# interfacez_r2_1.net
KiCad netlist of a schematic drawn in EAGLE
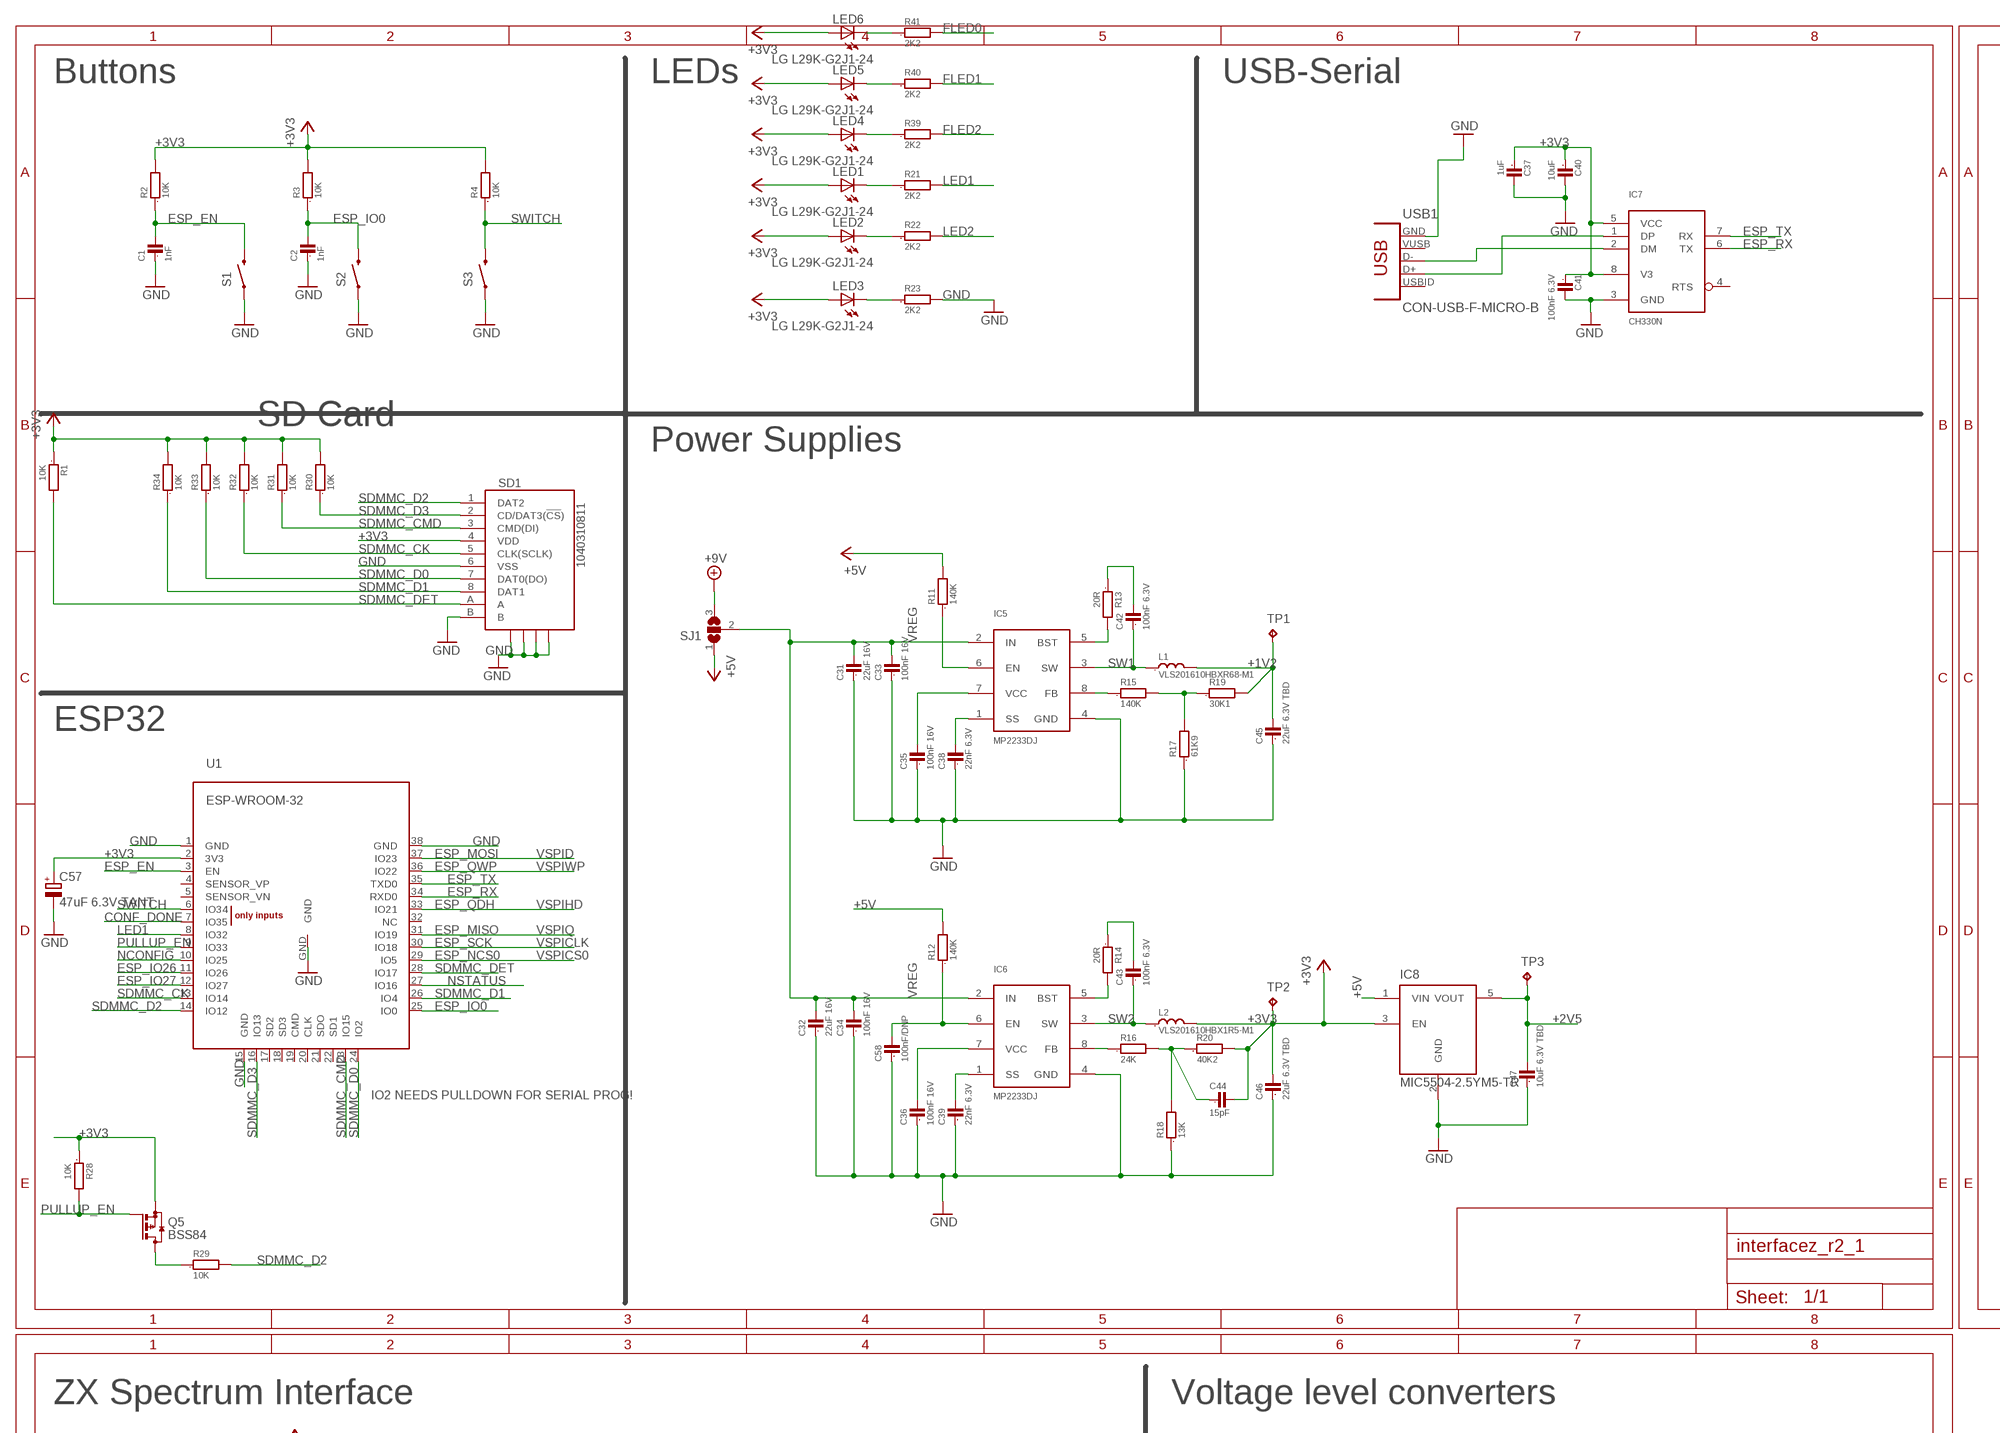
[diagram p0: schematic, sheet 1, part 1 of 3]
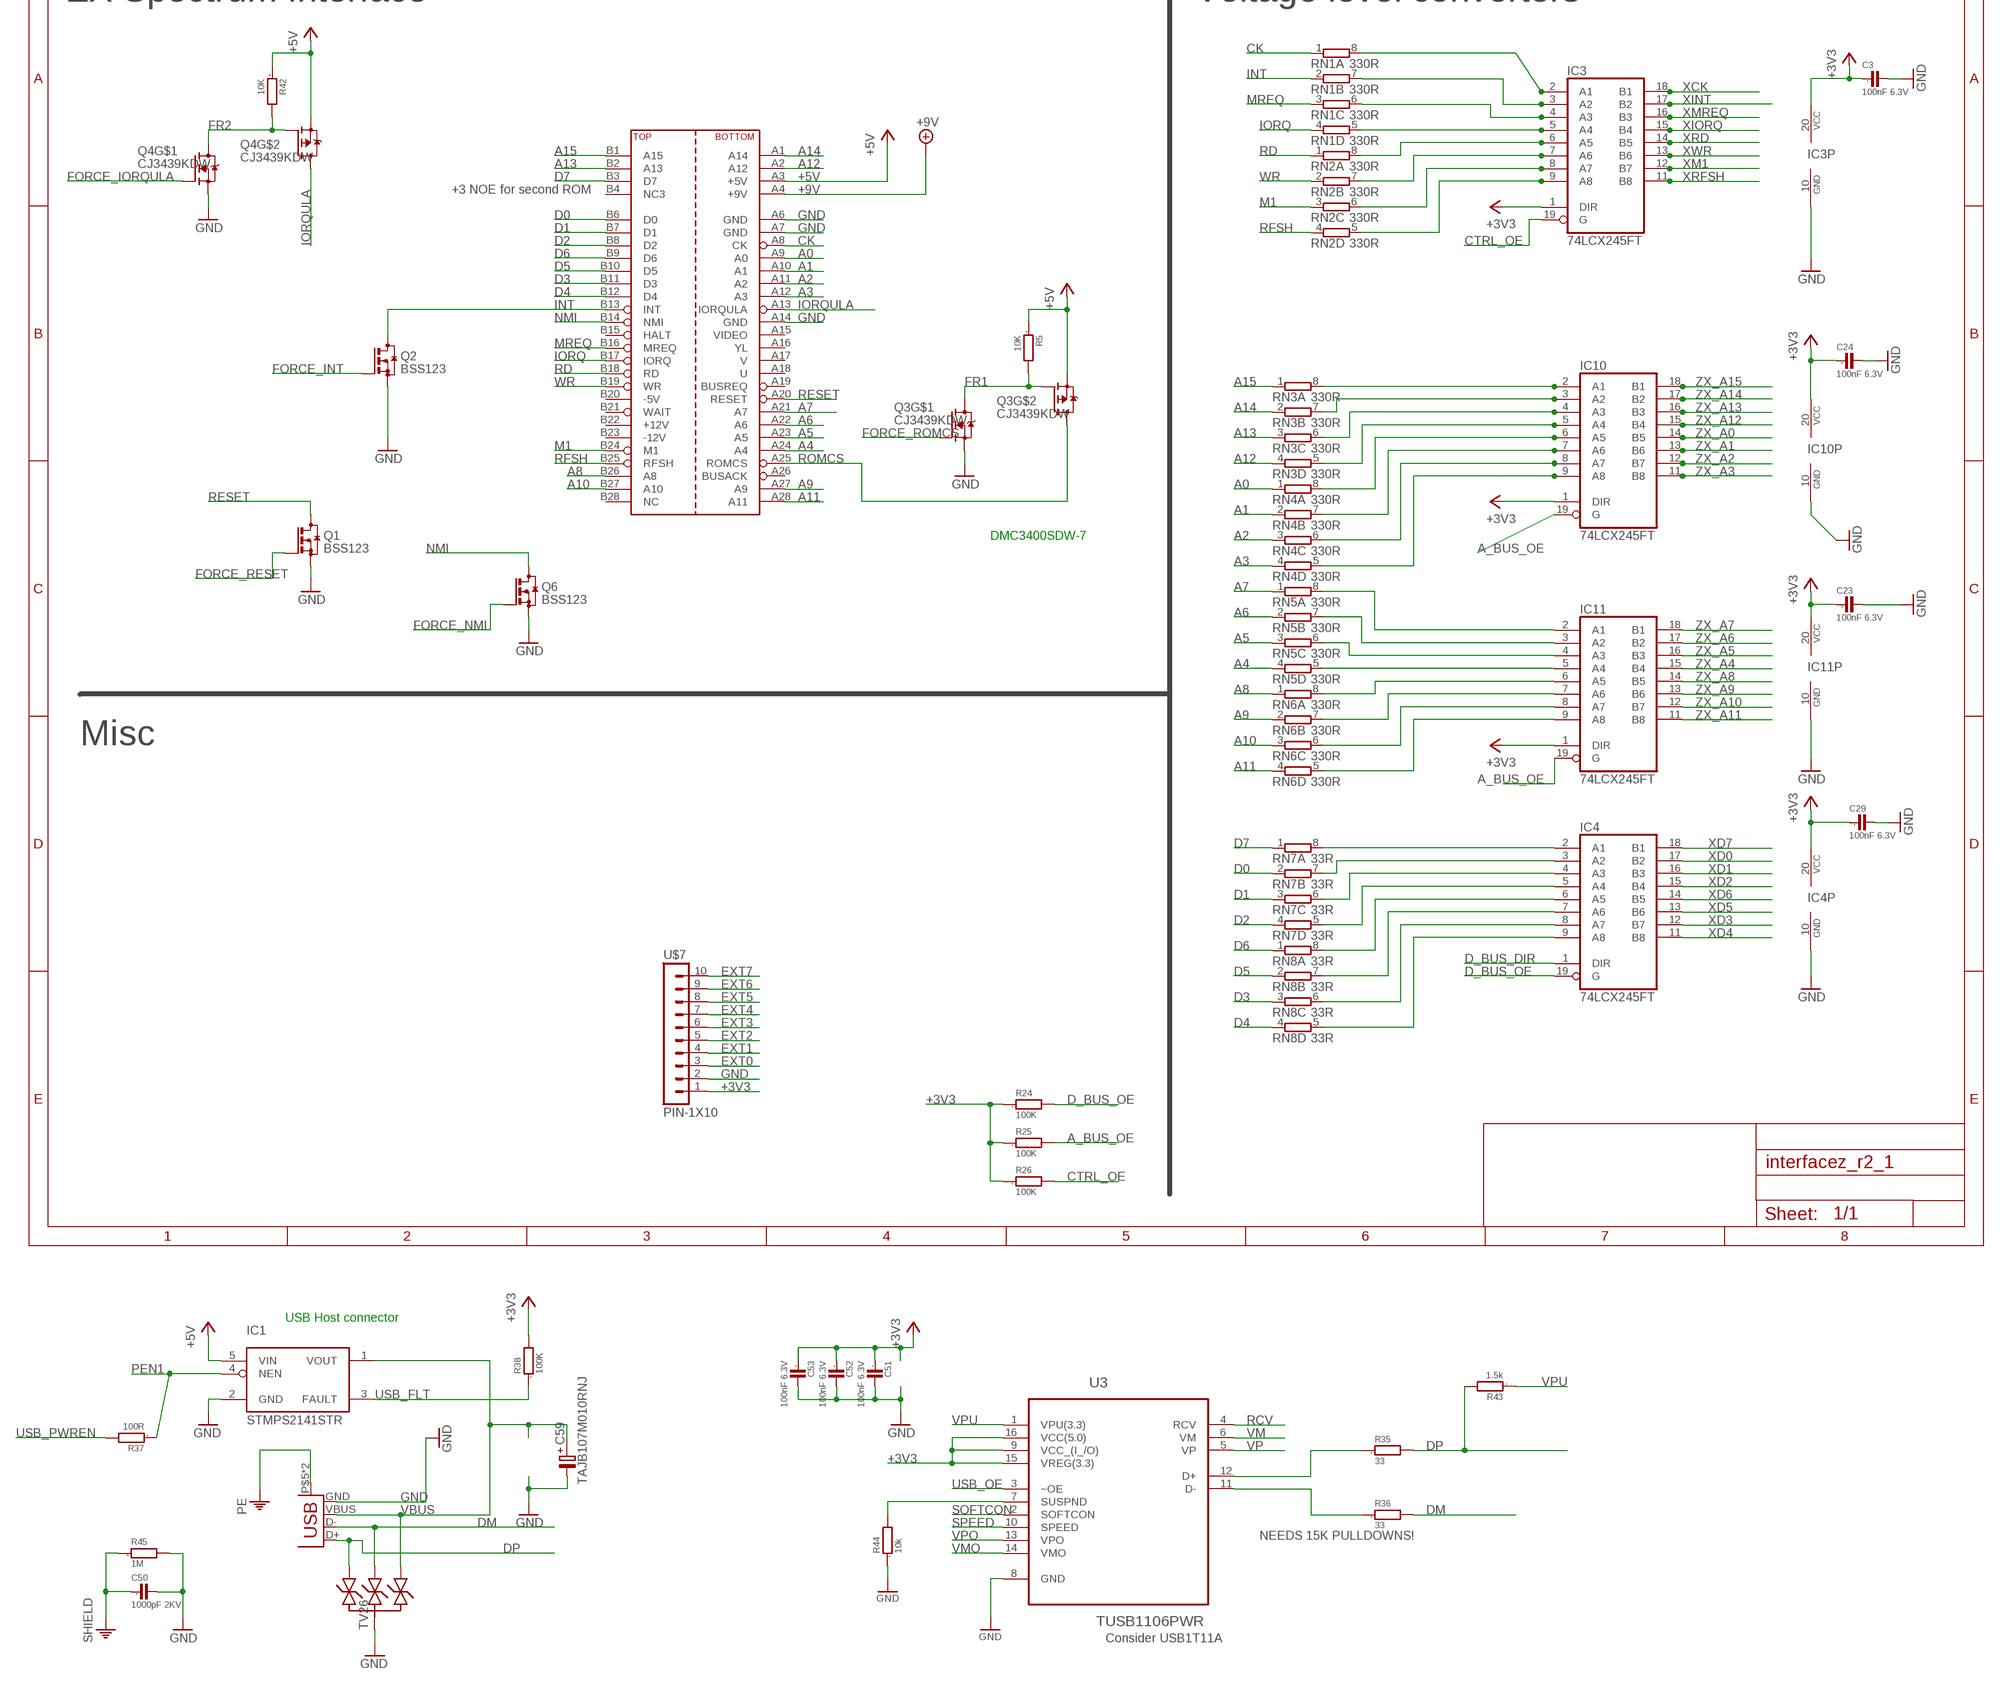
[diagram p1: schematic, sheet 1, part 2 of 3]
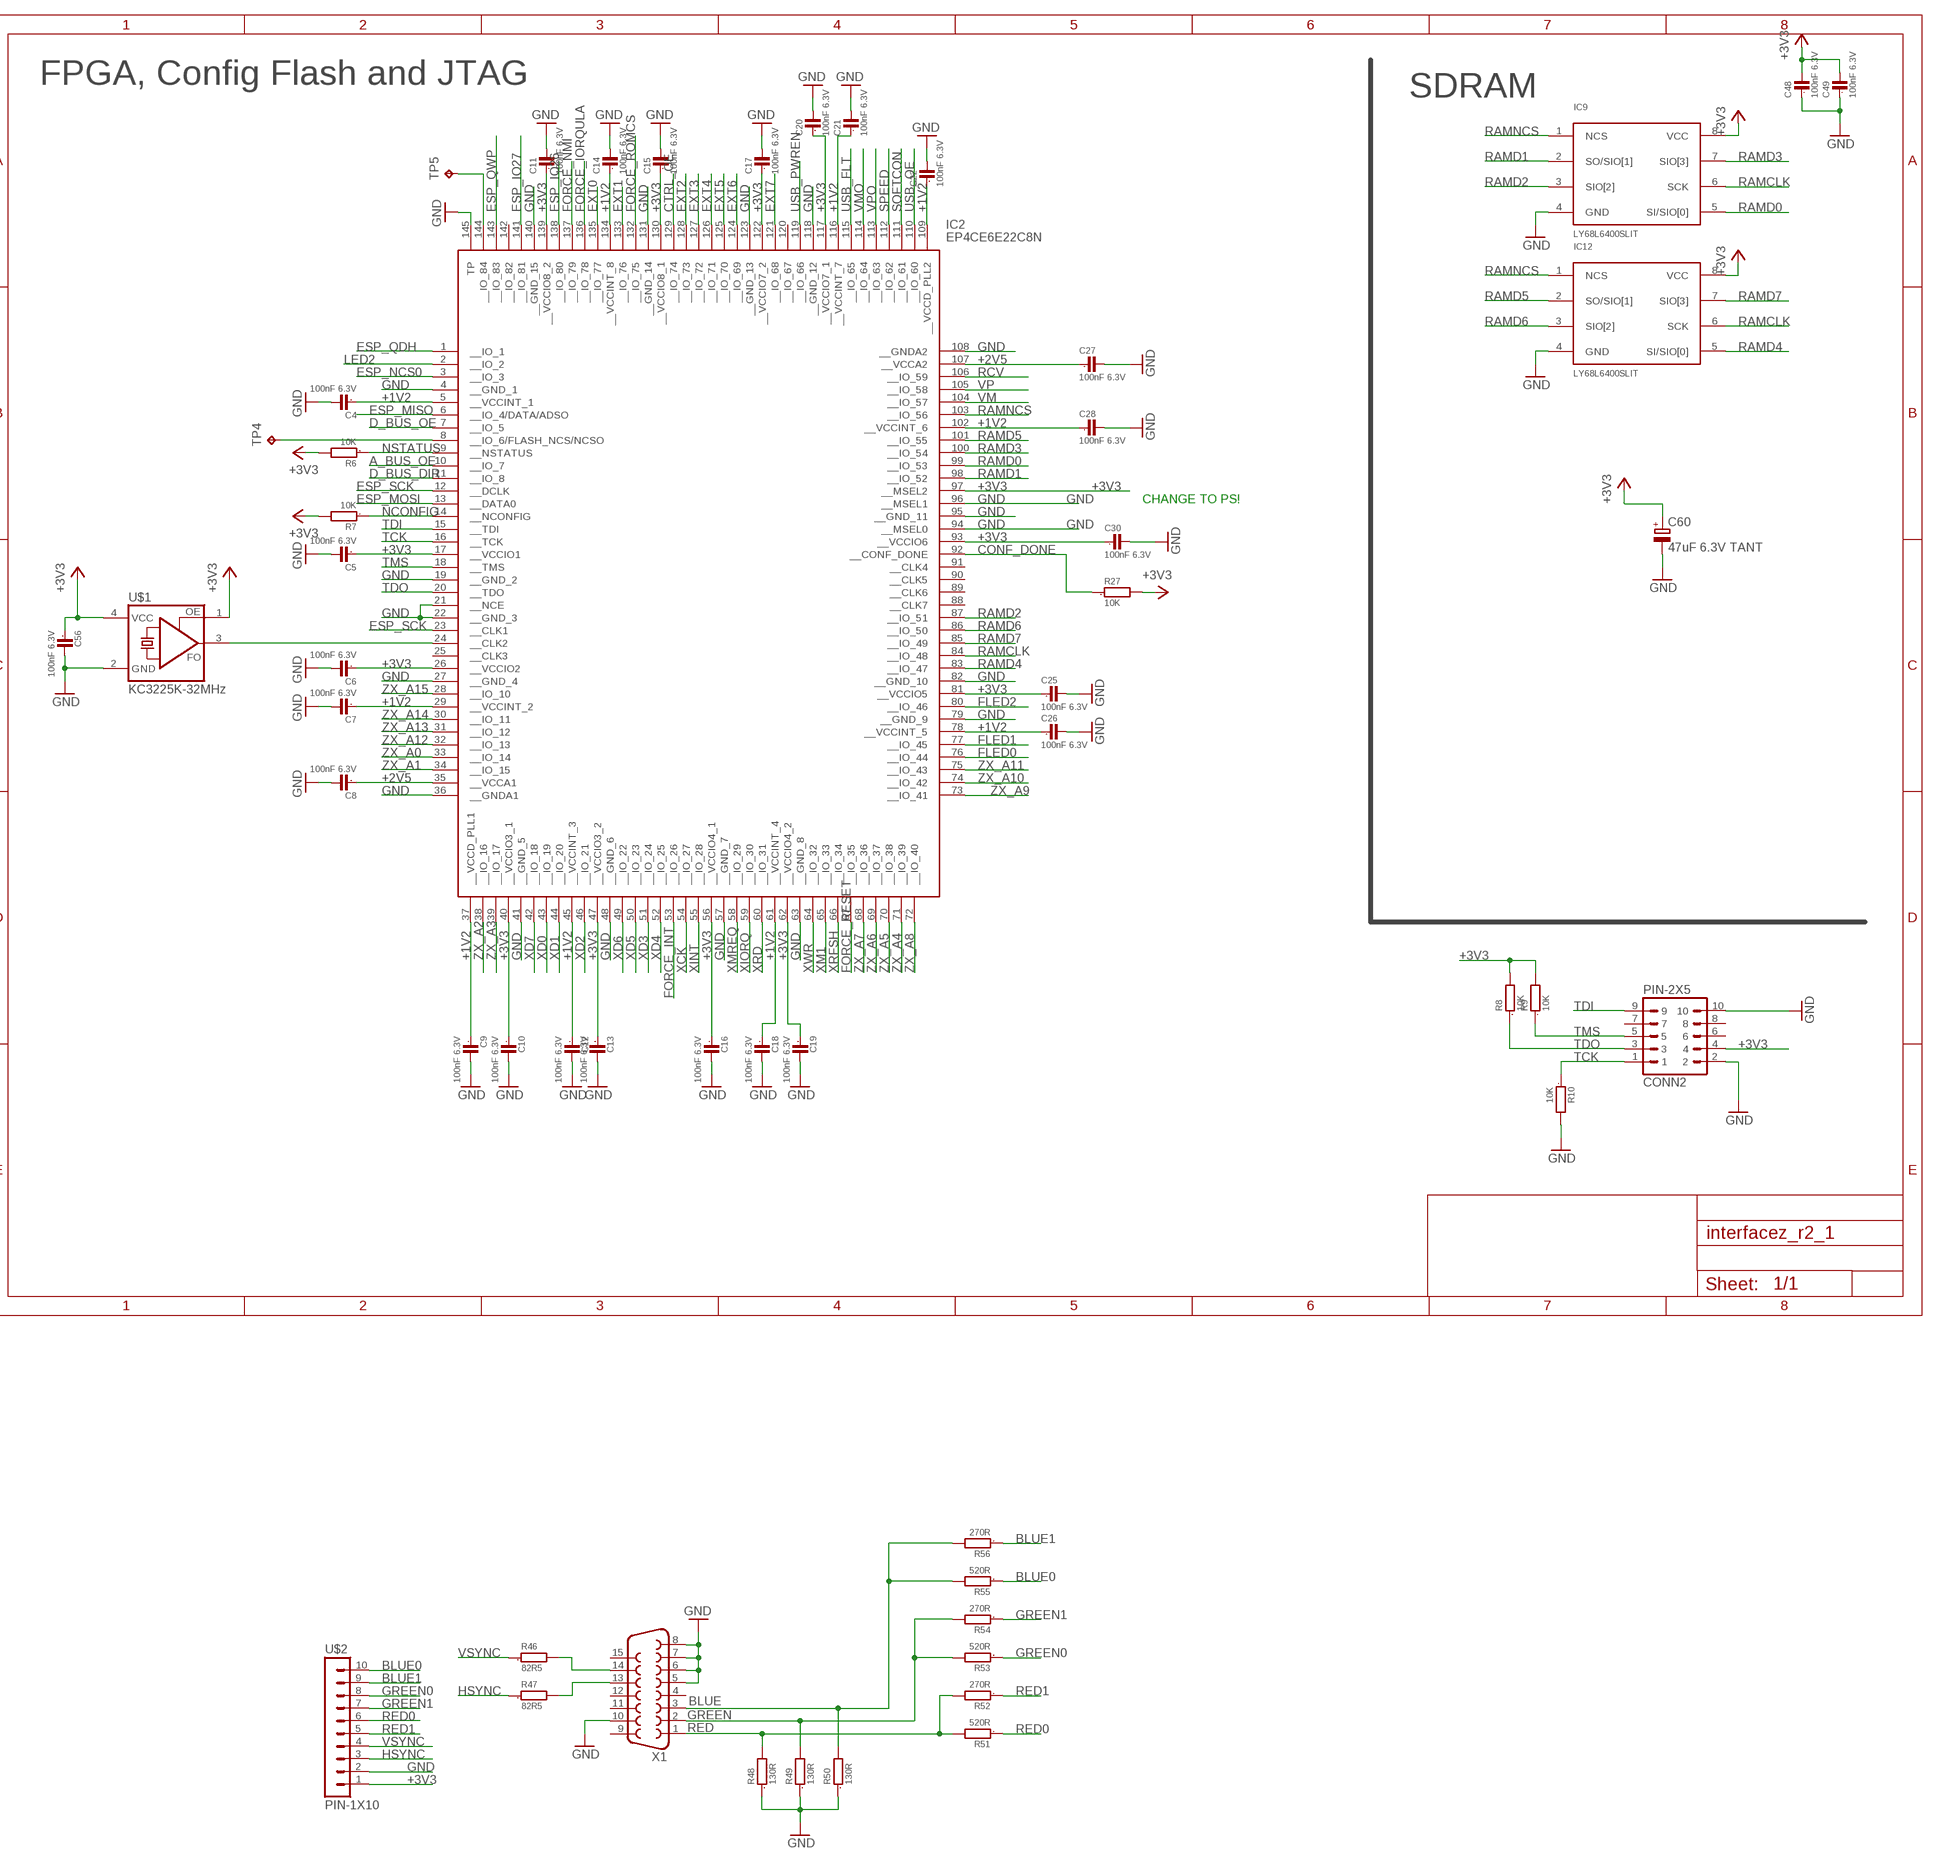
[diagram p2: schematic, sheet 1, part 3 of 3]

(export (version "E")
  (design (tool "Eeschema 10.0.6"))
  (components
    (comp (ref "C1")
      (value "1nF")
      (footprint "eagle-import:0603")
      (libsource (lib "eagle-import") (part "C0603"))
    )
    (comp (ref "C2")
      (value "1nF")
      (footprint "eagle-import:0603")
      (libsource (lib "eagle-import") (part "C0603"))
    )
    (comp (ref "C3")
      (value "100nF 6.3V")
      (footprint "eagle-import:0603")
      (libsource (lib "eagle-import") (part "C0603"))
    )
    (comp (ref "C4")
      (value "100nF 6.3V")
      (footprint "eagle-import:0603")
      (libsource (lib "eagle-import") (part "C0603"))
    )
    (comp (ref "C5")
      (value "100nF 6.3V")
      (footprint "eagle-import:0603")
      (libsource (lib "eagle-import") (part "C0603"))
    )
    (comp (ref "C6")
      (value "100nF 6.3V")
      (footprint "eagle-import:0603")
      (libsource (lib "eagle-import") (part "C0603"))
    )
    (comp (ref "C7")
      (value "100nF 6.3V")
      (footprint "eagle-import:0603")
      (libsource (lib "eagle-import") (part "C0603"))
    )
    (comp (ref "C8")
      (value "100nF 6.3V")
      (footprint "eagle-import:0603")
      (libsource (lib "eagle-import") (part "C0603"))
    )
    (comp (ref "C9")
      (value "100nF 6.3V")
      (footprint "eagle-import:0603")
      (libsource (lib "eagle-import") (part "C0603"))
    )
    (comp (ref "C10")
      (value "100nF 6.3V")
      (footprint "eagle-import:0603")
      (libsource (lib "eagle-import") (part "C0603"))
    )
    (comp (ref "C11")
      (value "100nF 6.3V")
      (footprint "eagle-import:0603")
      (libsource (lib "eagle-import") (part "C0603"))
    )
    (comp (ref "C12")
      (value "100nF 6.3V")
      (footprint "eagle-import:0603")
      (libsource (lib "eagle-import") (part "C0603"))
    )
    (comp (ref "C13")
      (value "100nF 6.3V")
      (footprint "eagle-import:0603")
      (libsource (lib "eagle-import") (part "C0603"))
    )
    (comp (ref "C14")
      (value "100nF 6.3V")
      (footprint "eagle-import:0603")
      (libsource (lib "eagle-import") (part "C0603"))
    )
    (comp (ref "C15")
      (value "100nF 6.3V")
      (footprint "eagle-import:0603")
      (libsource (lib "eagle-import") (part "C0603"))
    )
    (comp (ref "C16")
      (value "100nF 6.3V")
      (footprint "eagle-import:0603")
      (libsource (lib "eagle-import") (part "C0603"))
    )
    (comp (ref "C17")
      (value "100nF 6.3V")
      (footprint "eagle-import:0603")
      (libsource (lib "eagle-import") (part "C0603"))
    )
    (comp (ref "C18")
      (value "100nF 6.3V")
      (footprint "eagle-import:0603")
      (libsource (lib "eagle-import") (part "C0603"))
    )
    (comp (ref "C19")
      (value "100nF 6.3V")
      (footprint "eagle-import:0603")
      (libsource (lib "eagle-import") (part "C0603"))
    )
    (comp (ref "C20")
      (value "100nF 6.3V")
      (footprint "eagle-import:0603")
      (libsource (lib "eagle-import") (part "C0603"))
    )
    (comp (ref "C21")
      (value "100nF 6.3V")
      (footprint "eagle-import:0603")
      (libsource (lib "eagle-import") (part "C0603"))
    )
    (comp (ref "C22")
      (value "100nF 6.3V")
      (footprint "eagle-import:0603")
      (libsource (lib "eagle-import") (part "C0603"))
    )
    (comp (ref "C23")
      (value "100nF 6.3V")
      (footprint "eagle-import:0603")
      (libsource (lib "eagle-import") (part "C0603"))
    )
    (comp (ref "C24")
      (value "100nF 6.3V")
      (footprint "eagle-import:0603")
      (libsource (lib "eagle-import") (part "C0603"))
    )
    (comp (ref "C25")
      (value "100nF 6.3V")
      (footprint "eagle-import:0603")
      (libsource (lib "eagle-import") (part "C0603"))
    )
    (comp (ref "C26")
      (value "100nF 6.3V")
      (footprint "eagle-import:0603")
      (libsource (lib "eagle-import") (part "C0603"))
    )
    (comp (ref "C27")
      (value "100nF 6.3V")
      (footprint "eagle-import:0603")
      (libsource (lib "eagle-import") (part "C0603"))
    )
    (comp (ref "C28")
      (value "100nF 6.3V")
      (footprint "eagle-import:0603")
      (libsource (lib "eagle-import") (part "C0603"))
    )
    (comp (ref "C29")
      (value "100nF 6.3V")
      (footprint "eagle-import:0603")
      (libsource (lib "eagle-import") (part "C0603"))
    )
    (comp (ref "C30")
      (value "100nF 6.3V")
      (footprint "eagle-import:0603")
      (libsource (lib "eagle-import") (part "C0603"))
    )
    (comp (ref "C31")
      (value "22uF 16V")
      (footprint "eagle-import:1210")
      (libsource (lib "eagle-import") (part "C1210"))
    )
    (comp (ref "C32")
      (value "22uF 16V")
      (footprint "eagle-import:1210")
      (libsource (lib "eagle-import") (part "C1210"))
    )
    (comp (ref "C33")
      (value "100nF 16V")
      (footprint "eagle-import:0603")
      (libsource (lib "eagle-import") (part "C0603"))
    )
    (comp (ref "C34")
      (value "100nF 16V")
      (footprint "eagle-import:0603")
      (libsource (lib "eagle-import") (part "C0603"))
    )
    (comp (ref "C35")
      (value "100nF 16V")
      (footprint "eagle-import:0603")
      (libsource (lib "eagle-import") (part "C0603"))
    )
    (comp (ref "C36")
      (value "100nF 16V")
      (footprint "eagle-import:0603")
      (libsource (lib "eagle-import") (part "C0603"))
    )
    (comp (ref "C37")
      (value "1uF")
      (footprint "eagle-import:0603")
      (libsource (lib "eagle-import") (part "C0603"))
    )
    (comp (ref "C38")
      (value "22nF 6.3V")
      (footprint "eagle-import:0603")
      (libsource (lib "eagle-import") (part "C0603"))
    )
    (comp (ref "C39")
      (value "22nF 6.3V")
      (footprint "eagle-import:0603")
      (libsource (lib "eagle-import") (part "C0603"))
    )
    (comp (ref "C40")
      (value "10uF")
      (footprint "eagle-import:0603")
      (libsource (lib "eagle-import") (part "C0603"))
    )
    (comp (ref "C41")
      (value "100nF 6.3V")
      (footprint "eagle-import:0603")
      (libsource (lib "eagle-import") (part "C0603"))
    )
    (comp (ref "C42")
      (value "100nF 6.3V")
      (footprint "eagle-import:0603")
      (libsource (lib "eagle-import") (part "C0603"))
    )
    (comp (ref "C43")
      (value "100nF 6.3V")
      (footprint "eagle-import:0603")
      (libsource (lib "eagle-import") (part "C0603"))
    )
    (comp (ref "C44")
      (value "15pF")
      (footprint "eagle-import:0603")
      (libsource (lib "eagle-import") (part "C0603"))
    )
    (comp (ref "C45")
      (value "22uF 6.3V TBD")
      (footprint "eagle-import:0805")
      (libsource (lib "eagle-import") (part "C0805"))
    )
    (comp (ref "C46")
      (value "22uF 6.3V TBD")
      (footprint "eagle-import:0805")
      (libsource (lib "eagle-import") (part "C0805"))
    )
    (comp (ref "C47")
      (value "10uF 6.3V TBD")
      (footprint "eagle-import:0805")
      (libsource (lib "eagle-import") (part "C0805"))
    )
    (comp (ref "C48")
      (value "100nF 6.3V")
      (footprint "eagle-import:0603")
      (libsource (lib "eagle-import") (part "C0603"))
    )
    (comp (ref "C49")
      (value "100nF 6.3V")
      (footprint "eagle-import:0603")
      (libsource (lib "eagle-import") (part "C0603"))
    )
    (comp (ref "C50")
      (value "1000pF 2KV")
      (footprint "eagle-import:1210")
      (libsource (lib "eagle-import") (part "C1210"))
    )
    (comp (ref "C51")
      (value "100nF 6.3V")
      (footprint "eagle-import:0603")
      (libsource (lib "eagle-import") (part "C0603"))
    )
    (comp (ref "C52")
      (value "100nF 6.3V")
      (footprint "eagle-import:0603")
      (libsource (lib "eagle-import") (part "C0603"))
    )
    (comp (ref "C53")
      (value "100nF 6.3V")
      (footprint "eagle-import:0603")
      (libsource (lib "eagle-import") (part "C0603"))
    )
    (comp (ref "C56")
      (value "100nF 6.3V")
      (footprint "eagle-import:0603")
      (libsource (lib "eagle-import") (part "C0603"))
    )
    (comp (ref "C57")
      (value "47uF 6.3V TANT")
      (footprint "eagle-import:TANT_CASE_A")
      (libsource (lib "eagle-import") (part "TANT_CASE_A"))
    )
    (comp (ref "C58")
      (value "100nF/DNP")
      (footprint "eagle-import:0603")
      (libsource (lib "eagle-import") (part "C0603"))
    )
    (comp (ref "C59")
      (value "TAJB107M010RNJ")
      (footprint "eagle-import:TE-B-3528")
      (libsource (lib "eagle-import") (part "C-PR-SMD-TE-B"))
    )
    (comp (ref "C60")
      (value "47uF 6.3V TANT")
      (footprint "eagle-import:TANT_CASE_A")
      (libsource (lib "eagle-import") (part "TANT_CASE_A"))
    )
    (comp (ref "CONN1")
      (value "ZX_EDGE_DAUGHTERBOARD")
      (footprint "eagle-import:ZX-EDGE-DAUGHTERBOARD")
      (libsource (lib "eagle-import") (part "ZX_EDGE_DAUGHTERBOARD"))
    )
    (comp (ref "CONN2")
      (value "PIN-2X5")
      (footprint "eagle-import:PIN-2X5")
      (libsource (lib "eagle-import") (part "PIN-2X5"))
    )
    (comp (ref "IC1")
      (value "STMPS2141STR")
      (footprint "eagle-import:SOT23-5L")
      (libsource (lib "eagle-import") (part "STMPS2141STR"))
    )
    (comp (ref "IC2")
      (value "EP4CE6E22C8N")
      (footprint "eagle-import:QFP50P2200X2200X165-145N")
      (fields (field (name "MOUSER_PART_NUMBER") "989-EP4CE6E22C8N"))
      (libsource (lib "eagle-import") (part "EP4CE6E22C8N"))
    )
    (comp (ref "IC3")
      (value "74LCX245FT")
      (footprint "eagle-import:TSSOP20")
      (libsource (lib "eagle-import") (part "74245"))
    )
    (comp (ref "IC4")
      (value "74LCX245FT")
      (footprint "eagle-import:TSSOP20")
      (libsource (lib "eagle-import") (part "74245"))
    )
    (comp (ref "IC5")
      (value "MP2233DJ")
      (footprint "eagle-import:SOT23-8L")
      (libsource (lib "eagle-import") (part "MP2233DJ"))
    )
    (comp (ref "IC6")
      (value "MP2233DJ")
      (footprint "eagle-import:SOT23-8L")
      (libsource (lib "eagle-import") (part "MP2233DJ"))
    )
    (comp (ref "IC7")
      (value "CH330N")
      (footprint "eagle-import:SOIC8")
      (libsource (lib "eagle-import") (part "CH330N"))
    )
    (comp (ref "IC8")
      (value "MIC5504-2.5YM5-TR")
      (footprint "eagle-import:SOT23-5L")
      (libsource (lib "eagle-import") (part "MIC550X"))
    )
    (comp (ref "IC9")
      (value "LY68L6400SLIT")
      (footprint "eagle-import:SOIC8")
      (libsource (lib "eagle-import") (part "LY68L6400SLIT"))
    )
    (comp (ref "IC10")
      (value "74LCX245FT")
      (footprint "eagle-import:TSSOP20")
      (libsource (lib "eagle-import") (part "74245"))
    )
    (comp (ref "IC11")
      (value "74LCX245FT")
      (footprint "eagle-import:TSSOP20")
      (libsource (lib "eagle-import") (part "74245"))
    )
    (comp (ref "IC12")
      (value "LY68L6400SLIT")
      (footprint "eagle-import:SOIC8")
      (libsource (lib "eagle-import") (part "LY68L6400SLIT"))
    )
    (comp (ref "L1")
      (value "VLS201610HBXR68-M1")
      (footprint "eagle-import:IND_0806")
      (libsource (lib "eagle-import") (part "VLS201610HBXR68-M1"))
    )
    (comp (ref "L2")
      (value "VLS201610HBX1R5-M1")
      (footprint "eagle-import:IND_0806")
      (libsource (lib "eagle-import") (part "VLS201610HBX1R5-M1"))
    )
    (comp (ref "LED1")
      (value "LG L29K-G2J1-24")
      (footprint "eagle-import:LED-603")
      (libsource (lib "eagle-import") (part "LED-0603"))
    )
    (comp (ref "LED2")
      (value "LG L29K-G2J1-24")
      (footprint "eagle-import:LED-603")
      (libsource (lib "eagle-import") (part "LED-0603"))
    )
    (comp (ref "LED3")
      (value "LG L29K-G2J1-24")
      (footprint "eagle-import:LED-603")
      (libsource (lib "eagle-import") (part "LED-0603"))
    )
    (comp (ref "LED4")
      (value "LG L29K-G2J1-24")
      (footprint "eagle-import:LED-603")
      (libsource (lib "eagle-import") (part "LED-0603"))
    )
    (comp (ref "LED5")
      (value "LG L29K-G2J1-24")
      (footprint "eagle-import:LED-603")
      (libsource (lib "eagle-import") (part "LED-0603"))
    )
    (comp (ref "LED6")
      (value "LG L29K-G2J1-24")
      (footprint "eagle-import:LED-603")
      (libsource (lib "eagle-import") (part "LED-0603"))
    )
    (comp (ref "Q1")
      (value "BSS123")
      (footprint "eagle-import:SOT23")
      (libsource (lib "eagle-import") (part "BSS123"))
    )
    (comp (ref "Q2")
      (value "BSS123")
      (footprint "eagle-import:SOT23")
      (libsource (lib "eagle-import") (part "BSS123"))
    )
    (comp (ref "Q3")
      (value "CJ3439KDW")
      (footprint "eagle-import:SC70-6")
      (libsource (lib "eagle-import") (part "CJ3439KDW"))
    )
    (comp (ref "Q4")
      (value "CJ3439KDW")
      (footprint "eagle-import:SC70-6")
      (libsource (lib "eagle-import") (part "CJ3439KDW"))
    )
    (comp (ref "Q5")
      (value "BSS84")
      (footprint "eagle-import:SOT23")
      (libsource (lib "eagle-import") (part "BSS84"))
    )
    (comp (ref "Q6")
      (value "BSS123")
      (footprint "eagle-import:SOT23")
      (libsource (lib "eagle-import") (part "BSS123"))
    )
    (comp (ref "R1")
      (value "10K")
      (footprint "eagle-import:0603")
      (libsource (lib "eagle-import") (part "R0603"))
    )
    (comp (ref "R2")
      (value "10K")
      (footprint "eagle-import:0603")
      (libsource (lib "eagle-import") (part "R0603"))
    )
    (comp (ref "R3")
      (value "10K")
      (footprint "eagle-import:0603")
      (libsource (lib "eagle-import") (part "R0603"))
    )
    (comp (ref "R4")
      (value "10K")
      (footprint "eagle-import:0603")
      (libsource (lib "eagle-import") (part "R0603"))
    )
    (comp (ref "R5")
      (value "10K")
      (footprint "eagle-import:0603")
      (libsource (lib "eagle-import") (part "R0603"))
    )
    (comp (ref "R6")
      (value "10K")
      (footprint "eagle-import:0603")
      (libsource (lib "eagle-import") (part "R0603"))
    )
    (comp (ref "R7")
      (value "10K")
      (footprint "eagle-import:0603")
      (libsource (lib "eagle-import") (part "R0603"))
    )
    (comp (ref "R8")
      (value "10K")
      (footprint "eagle-import:0603")
      (libsource (lib "eagle-import") (part "R0603"))
    )
    (comp (ref "R9")
      (value "10K")
      (footprint "eagle-import:0603")
      (libsource (lib "eagle-import") (part "R0603"))
    )
    (comp (ref "R10")
      (value "10K")
      (footprint "eagle-import:0603")
      (libsource (lib "eagle-import") (part "R0603"))
    )
    (comp (ref "R11")
      (value "140K")
      (footprint "eagle-import:0603")
      (libsource (lib "eagle-import") (part "R0603"))
    )
    (comp (ref "R12")
      (value "140K")
      (footprint "eagle-import:0603")
      (libsource (lib "eagle-import") (part "R0603"))
    )
    (comp (ref "R13")
      (value "20R")
      (footprint "eagle-import:0603")
      (libsource (lib "eagle-import") (part "R0603"))
    )
    (comp (ref "R14")
      (value "20R")
      (footprint "eagle-import:0603")
      (libsource (lib "eagle-import") (part "R0603"))
    )
    (comp (ref "R15")
      (value "140K")
      (footprint "eagle-import:0603")
      (libsource (lib "eagle-import") (part "R0603"))
    )
    (comp (ref "R16")
      (value "24K")
      (footprint "eagle-import:0603")
      (libsource (lib "eagle-import") (part "R0603"))
    )
    (comp (ref "R17")
      (value "61K9")
      (footprint "eagle-import:0603")
      (libsource (lib "eagle-import") (part "R0603"))
    )
    (comp (ref "R18")
      (value "13K")
      (footprint "eagle-import:0603")
      (libsource (lib "eagle-import") (part "R0603"))
    )
    (comp (ref "R19")
      (value "30K1")
      (footprint "eagle-import:0603")
      (libsource (lib "eagle-import") (part "R0603"))
    )
    (comp (ref "R20")
      (value "40K2")
      (footprint "eagle-import:0603")
      (libsource (lib "eagle-import") (part "R0603"))
    )
    (comp (ref "R21")
      (value "2K2")
      (footprint "eagle-import:0603")
      (libsource (lib "eagle-import") (part "R0603"))
    )
    (comp (ref "R22")
      (value "2K2")
      (footprint "eagle-import:0603")
      (libsource (lib "eagle-import") (part "R0603"))
    )
    (comp (ref "R23")
      (value "2K2")
      (footprint "eagle-import:0603")
      (libsource (lib "eagle-import") (part "R0603"))
    )
    (comp (ref "R24")
      (value "100K")
      (footprint "eagle-import:0603")
      (libsource (lib "eagle-import") (part "R0603"))
    )
    (comp (ref "R25")
      (value "100K")
      (footprint "eagle-import:0603")
      (libsource (lib "eagle-import") (part "R0603"))
    )
    (comp (ref "R26")
      (value "100K")
      (footprint "eagle-import:0603")
      (libsource (lib "eagle-import") (part "R0603"))
    )
    (comp (ref "R27")
      (value "10K")
      (footprint "eagle-import:0603")
      (libsource (lib "eagle-import") (part "R0603"))
    )
    (comp (ref "R28")
      (value "10K")
      (footprint "eagle-import:0603")
      (libsource (lib "eagle-import") (part "R0603"))
    )
    (comp (ref "R29")
      (value "10K")
      (footprint "eagle-import:0603")
      (libsource (lib "eagle-import") (part "R0603"))
    )
    (comp (ref "R30")
      (value "10K")
      (footprint "eagle-import:0603")
      (libsource (lib "eagle-import") (part "R0603"))
    )
    (comp (ref "R31")
      (value "10K")
      (footprint "eagle-import:0603")
      (libsource (lib "eagle-import") (part "R0603"))
    )
    (comp (ref "R32")
      (value "10K")
      (footprint "eagle-import:0603")
      (libsource (lib "eagle-import") (part "R0603"))
    )
    (comp (ref "R33")
      (value "10K")
      (footprint "eagle-import:0603")
      (libsource (lib "eagle-import") (part "R0603"))
    )
    (comp (ref "R34")
      (value "10K")
      (footprint "eagle-import:0603")
      (libsource (lib "eagle-import") (part "R0603"))
    )
    (comp (ref "R35")
      (value "33")
      (footprint "eagle-import:0603")
      (libsource (lib "eagle-import") (part "R0603"))
    )
    (comp (ref "R36")
      (value "33")
      (footprint "eagle-import:0603")
      (libsource (lib "eagle-import") (part "R0603"))
    )
    (comp (ref "R37")
      (value "100R")
      (footprint "eagle-import:0603")
      (libsource (lib "eagle-import") (part "R0603"))
    )
    (comp (ref "R38")
      (value "100K")
      (footprint "eagle-import:0603")
      (libsource (lib "eagle-import") (part "R0603"))
    )
    (comp (ref "R39")
      (value "2K2")
      (footprint "eagle-import:0603")
      (libsource (lib "eagle-import") (part "R0603"))
    )
    (comp (ref "R40")
      (value "2K2")
      (footprint "eagle-import:0603")
      (libsource (lib "eagle-import") (part "R0603"))
    )
    (comp (ref "R41")
      (value "2K2")
      (footprint "eagle-import:0603")
      (libsource (lib "eagle-import") (part "R0603"))
    )
    (comp (ref "R42")
      (value "10K")
      (footprint "eagle-import:0603")
      (libsource (lib "eagle-import") (part "R0603"))
    )
    (comp (ref "R43")
      (value "1.5k")
      (footprint "eagle-import:0603")
      (libsource (lib "eagle-import") (part "R0603"))
    )
    (comp (ref "R44")
      (value "10k")
      (footprint "eagle-import:0603")
      (libsource (lib "eagle-import") (part "R0603"))
    )
    (comp (ref "R45")
      (value "1M")
      (footprint "eagle-import:0805")
      (libsource (lib "eagle-import") (part "R0805"))
    )
    (comp (ref "R46")
      (value "82R5")
      (footprint "eagle-import:0603")
      (libsource (lib "eagle-import") (part "R0603"))
    )
    (comp (ref "R47")
      (value "82R5")
      (footprint "eagle-import:0603")
      (libsource (lib "eagle-import") (part "R0603"))
    )
    (comp (ref "R48")
      (value "130R")
      (footprint "eagle-import:0603")
      (libsource (lib "eagle-import") (part "R0603"))
    )
    (comp (ref "R49")
      (value "130R")
      (footprint "eagle-import:0603")
      (libsource (lib "eagle-import") (part "R0603"))
    )
    (comp (ref "R50")
      (value "130R")
      (footprint "eagle-import:0603")
      (libsource (lib "eagle-import") (part "R0603"))
    )
    (comp (ref "R51")
      (value "520R")
      (footprint "eagle-import:0603")
      (libsource (lib "eagle-import") (part "R0603"))
    )
    (comp (ref "R52")
      (value "270R")
      (footprint "eagle-import:0603")
      (libsource (lib "eagle-import") (part "R0603"))
    )
    (comp (ref "R53")
      (value "520R")
      (footprint "eagle-import:0603")
      (libsource (lib "eagle-import") (part "R0603"))
    )
    (comp (ref "R54")
      (value "270R")
      (footprint "eagle-import:0603")
      (libsource (lib "eagle-import") (part "R0603"))
    )
    (comp (ref "R55")
      (value "520R")
      (footprint "eagle-import:0603")
      (libsource (lib "eagle-import") (part "R0603"))
    )
    (comp (ref "R56")
      (value "270R")
      (footprint "eagle-import:0603")
      (libsource (lib "eagle-import") (part "R0603"))
    )
    (comp (ref "RN1")
      (value "330R")
      (footprint "eagle-import:EXB28V")
      (libsource (lib "eagle-import") (part "4R-NEXB28V"))
    )
    (comp (ref "RN2")
      (value "330R")
      (footprint "eagle-import:EXB28V")
      (libsource (lib "eagle-import") (part "4R-NEXB28V"))
    )
    (comp (ref "RN3")
      (value "330R")
      (footprint "eagle-import:EXB28V")
      (libsource (lib "eagle-import") (part "4R-NEXB28V"))
    )
    (comp (ref "RN4")
      (value "330R")
      (footprint "eagle-import:EXB28V")
      (libsource (lib "eagle-import") (part "4R-NEXB28V"))
    )
    (comp (ref "RN5")
      (value "330R")
      (footprint "eagle-import:EXB28V")
      (libsource (lib "eagle-import") (part "4R-NEXB28V"))
    )
    (comp (ref "RN6")
      (value "330R")
      (footprint "eagle-import:EXB28V")
      (libsource (lib "eagle-import") (part "4R-NEXB28V"))
    )
    (comp (ref "RN7")
      (value "33R")
      (footprint "eagle-import:EXB28V")
      (libsource (lib "eagle-import") (part "4R-NEXB28V"))
    )
    (comp (ref "RN8")
      (value "33R")
      (footprint "eagle-import:EXB28V")
      (libsource (lib "eagle-import") (part "4R-NEXB28V"))
    )
    (comp (ref "S1")
      (value "SWITCHES_SMD-4")
      (footprint "eagle-import:TACTILE_SWITCH_TALL")
      (libsource (lib "eagle-import") (part "SWITCHES_SMD-4"))
    )
    (comp (ref "S2")
      (value "SWITCHES_SMD-4")
      (footprint "eagle-import:TACTILE_SWITCH_TALL")
      (libsource (lib "eagle-import") (part "SWITCHES_SMD-4"))
    )
    (comp (ref "S3")
      (value "SWITCHES_SMD-4")
      (footprint "eagle-import:TACTILE_SWITCH_TALL")
      (libsource (lib "eagle-import") (part "SWITCHES_SMD-4"))
    )
    (comp (ref "SD1")
      (value "1040310811")
      (footprint "eagle-import:1040310811")
      (libsource (lib "eagle-import") (part "1040310811"))
    )
    (comp (ref "SJ1")
      (value "SJ2W")
      (footprint "eagle-import:SJ_2")
      (libsource (lib "eagle-import") (part "SJ2W"))
    )
    (comp (ref "TP1")
      (value "TPTP12R")
      (footprint "eagle-import:TP12R")
      (libsource (lib "eagle-import") (part "TPTP12R"))
    )
    (comp (ref "TP2")
      (value "TPTP12R")
      (footprint "eagle-import:TP12R")
      (libsource (lib "eagle-import") (part "TPTP12R"))
    )
    (comp (ref "TP3")
      (value "TPTP12R")
      (footprint "eagle-import:TP12R")
      (libsource (lib "eagle-import") (part "TPTP12R"))
    )
    (comp (ref "TP4")
      (value "TPTP08R")
      (footprint "eagle-import:TP08R")
      (libsource (lib "eagle-import") (part "TPTP08R"))
    )
    (comp (ref "TP5")
      (value "TPTP08R")
      (footprint "eagle-import:TP08R")
      (libsource (lib "eagle-import") (part "TPTP08R"))
    )
    (comp (ref "TV26")
      (value "SP0503BAHT")
      (footprint "eagle-import:SP0503")
      (libsource (lib "eagle-import") (part "SP0503BAHT"))
    )
    (comp (ref "U$1")
      (value "KC3225K-32MHz")
      (footprint "eagle-import:KC3225K")
      (libsource (lib "eagle-import") (part "KC3225K"))
    )
    (comp (ref "U$2")
      (value "PIN-1X10")
      (footprint "eagle-import:PIN-1X10")
      (libsource (lib "eagle-import") (part "PIN-1X10"))
    )
    (comp (ref "U$7")
      (value "PIN-1X10")
      (footprint "eagle-import:PIN-1X10")
      (libsource (lib "eagle-import") (part "PIN-1X10"))
    )
    (comp (ref "U1")
      (value "ESP-WROOM-32")
      (footprint "eagle-import:ESP-WROOM-32")
      (libsource (lib "eagle-import") (part "ESP-WROOM-32"))
    )
    (comp (ref "U3")
      (value "TUSB1106PWR")
      (footprint "eagle-import:SOP65P640X120-16N")
      (libsource (lib "eagle-import") (part "TUSB1106PWR"))
    )
    (comp (ref "USB1")
      (value "CON-USB-F-MICRO-B")
      (footprint "eagle-import:CONN_USB_MICRO-B")
      (libsource (lib "eagle-import") (part "CON-USB-F-MICRO-B"))
    )
    (comp (ref "USB2")
      (value "USB-A-H")
      (footprint "eagle-import:USB-A-H")
      (libsource (lib "eagle-import") (part "USB-A-H"))
    )
    (comp (ref "X1")
      (value "F15HDH")
      (footprint "eagle-import:HDF15H")
      (libsource (lib "eagle-import") (part "F15HDH"))
    )
  )
  (nets
    (net (code "1") (name "+3V3") (class "Default")
      (node (ref "C10") (pin "1") (pinfunction "1_1") (pintype "passive"))
      (node (ref "C11") (pin "1") (pinfunction "1_1") (pintype "passive"))
      (node (ref "C13") (pin "1") (pinfunction "1_1") (pintype "passive"))
      (node (ref "C15") (pin "1") (pinfunction "1_1") (pintype "passive"))
      (node (ref "C16") (pin "1") (pinfunction "1_1") (pintype "passive"))
      (node (ref "C17") (pin "1") (pinfunction "1_1") (pintype "passive"))
      (node (ref "C19") (pin "1") (pinfunction "1_1") (pintype "passive"))
      (node (ref "C20") (pin "1") (pinfunction "1_1") (pintype "passive"))
      (node (ref "C23") (pin "1") (pinfunction "1_1") (pintype "passive"))
      (node (ref "C24") (pin "1") (pinfunction "1_1") (pintype "passive"))
      (node (ref "C25") (pin "1") (pinfunction "1_1") (pintype "passive"))
      (node (ref "C29") (pin "1") (pinfunction "1_1") (pintype "passive"))
      (node (ref "C3") (pin "1") (pinfunction "1_1") (pintype "passive"))
      (node (ref "C30") (pin "1") (pinfunction "1_1") (pintype "passive"))
      (node (ref "C37") (pin "1") (pinfunction "1_1") (pintype "passive"))
      (node (ref "C40") (pin "1") (pinfunction "1_1") (pintype "passive"))
      (node (ref "C41") (pin "1") (pinfunction "1_1") (pintype "passive"))
      (node (ref "C44") (pin "2") (pinfunction "2_2") (pintype "passive"))
      (node (ref "C46") (pin "2") (pinfunction "2_2") (pintype "passive"))
      (node (ref "C48") (pin "2") (pinfunction "2_2") (pintype "passive"))
      (node (ref "C49") (pin "2") (pinfunction "2_2") (pintype "passive"))
      (node (ref "C5") (pin "1") (pinfunction "1_1") (pintype "passive"))
      (node (ref "C51") (pin "1") (pinfunction "1_1") (pintype "passive"))
      (node (ref "C52") (pin "1") (pinfunction "1_1") (pintype "passive"))
      (node (ref "C53") (pin "1") (pinfunction "1_1") (pintype "passive"))
      (node (ref "C56") (pin "1") (pinfunction "1_1") (pintype "passive"))
      (node (ref "C57") (pin "PLUS") (pinfunction "+_PLUS") (pintype "passive"))
      (node (ref "C6") (pin "1") (pinfunction "1_1") (pintype "passive"))
      (node (ref "C60") (pin "PLUS") (pinfunction "+_PLUS") (pintype "passive"))
      (node (ref "CONN2") (pin "4") (pinfunction "4_4") (pintype "passive"))
      (node (ref "IC10") (pin "1") (pinfunction "DIR_1") (pintype "input"))
      (node (ref "IC10") (pin "20") (pinfunction "VCC_20") (pintype "power_in"))
      (node (ref "IC11") (pin "1") (pinfunction "DIR_1") (pintype "input"))
      (node (ref "IC11") (pin "20") (pinfunction "VCC_20") (pintype "power_in"))
      (node (ref "IC12") (pin "8") (pinfunction "VCC_8") (pintype "power_in"))
      (node (ref "IC2") (pin "117") (pinfunction "__VCCIO7_1_117") (pintype "power_in"))
      (node (ref "IC2") (pin "122") (pinfunction "__VCCIO7_2_122") (pintype "power_in"))
      (node (ref "IC2") (pin "130") (pinfunction "__VCCIO8_1_130") (pintype "power_in"))
      (node (ref "IC2") (pin "139") (pinfunction "__VCCIO8_2_139") (pintype "power_in"))
      (node (ref "IC2") (pin "17") (pinfunction "__VCCIO1_17") (pintype "power_in"))
      (node (ref "IC2") (pin "26") (pinfunction "__VCCIO2_26") (pintype "power_in"))
      (node (ref "IC2") (pin "40") (pinfunction "__VCCIO3_1_40") (pintype "power_in"))
      (node (ref "IC2") (pin "47") (pinfunction "__VCCIO3_2_47") (pintype "power_in"))
      (node (ref "IC2") (pin "56") (pinfunction "__VCCIO4_1_56") (pintype "power_in"))
      (node (ref "IC2") (pin "62") (pinfunction "__VCCIO4_2_62") (pintype "power_in"))
      (node (ref "IC2") (pin "81") (pinfunction "__VCCIO5_81") (pintype "power_in"))
      (node (ref "IC2") (pin "93") (pinfunction "__VCCIO6_93") (pintype "power_in"))
      (node (ref "IC2") (pin "97") (pinfunction "__MSEL2_97") (pintype "bidirectional"))
      (node (ref "IC3") (pin "1") (pinfunction "DIR_1") (pintype "input"))
      (node (ref "IC3") (pin "20") (pinfunction "VCC_20") (pintype "power_in"))
      (node (ref "IC4") (pin "20") (pinfunction "VCC_20") (pintype "power_in"))
      (node (ref "IC7") (pin "5") (pinfunction "VCC_5") (pintype "power_in"))
      (node (ref "IC7") (pin "8") (pinfunction "V3_8") (pintype "passive"))
      (node (ref "IC8") (pin "3") (pinfunction "EN_3") (pintype "input"))
      (node (ref "IC9") (pin "8") (pinfunction "VCC_8") (pintype "power_in"))
      (node (ref "L2") (pin "P$2") (pinfunction "2_P$2") (pintype "passive"))
      (node (ref "LED1") (pin "A") (pinfunction "A_A") (pintype "passive"))
      (node (ref "LED2") (pin "A") (pinfunction "A_A") (pintype "passive"))
      (node (ref "LED3") (pin "A") (pinfunction "A_A") (pintype "passive"))
      (node (ref "LED4") (pin "A") (pinfunction "A_A") (pintype "passive"))
      (node (ref "LED5") (pin "A") (pinfunction "A_A") (pintype "passive"))
      (node (ref "LED6") (pin "A") (pinfunction "A_A") (pintype "passive"))
      (node (ref "Q5") (pin "2") (pinfunction "S_2") (pintype "passive"))
      (node (ref "R1") (pin "1") (pinfunction "1_1") (pintype "passive"))
      (node (ref "R2") (pin "2") (pinfunction "2_2") (pintype "passive"))
      (node (ref "R20") (pin "2") (pinfunction "2_2") (pintype "passive"))
      (node (ref "R24") (pin "1") (pinfunction "1_1") (pintype "passive"))
      (node (ref "R25") (pin "1") (pinfunction "1_1") (pintype "passive"))
      (node (ref "R26") (pin "1") (pinfunction "1_1") (pintype "passive"))
      (node (ref "R27") (pin "2") (pinfunction "2_2") (pintype "passive"))
      (node (ref "R28") (pin "1") (pinfunction "1_1") (pintype "passive"))
      (node (ref "R3") (pin "2") (pinfunction "2_2") (pintype "passive"))
      (node (ref "R30") (pin "2") (pinfunction "2_2") (pintype "passive"))
      (node (ref "R31") (pin "2") (pinfunction "2_2") (pintype "passive"))
      (node (ref "R32") (pin "2") (pinfunction "2_2") (pintype "passive"))
      (node (ref "R33") (pin "2") (pinfunction "2_2") (pintype "passive"))
      (node (ref "R34") (pin "2") (pinfunction "2_2") (pintype "passive"))
      (node (ref "R38") (pin "2") (pinfunction "2_2") (pintype "passive"))
      (node (ref "R4") (pin "2") (pinfunction "2_2") (pintype "passive"))
      (node (ref "R6") (pin "2") (pinfunction "2_2") (pintype "passive"))
      (node (ref "R7") (pin "2") (pinfunction "2_2") (pintype "passive"))
      (node (ref "R8") (pin "2") (pinfunction "2_2") (pintype "passive"))
      (node (ref "R9") (pin "2") (pinfunction "2_2") (pintype "passive"))
      (node (ref "SD1") (pin "4") (pinfunction "VDD_4") (pintype "power_in"))
      (node (ref "TP2") (pin "TP") (pinfunction "TP_TP") (pintype "input"))
      (node (ref "U$1") (pin "1") (pinfunction "OE_1") (pintype "input"))
      (node (ref "U$1") (pin "4") (pinfunction "VCC_4") (pintype "power_in"))
      (node (ref "U$2") (pin "1") (pinfunction "1_1") (pintype "passive"))
      (node (ref "U$7") (pin "1") (pinfunction "1_1") (pintype "passive"))
      (node (ref "U1") (pin "2") (pinfunction "3V3_2") (pintype "bidirectional"))
      (node (ref "U3") (pin "15") (pinfunction "VREG(3.3)_15") (pintype "power_in"))
      (node (ref "U3") (pin "16") (pinfunction "VCC(5.0)_16") (pintype "power_in"))
      (node (ref "U3") (pin "9") (pinfunction "VCC_(I_/O)_9") (pintype "power_in"))
    )
    (net (code "2") (name "+5V") (class "Default")
      (node (ref "CONN1") (pin "A3") (pinfunction "+5V_A3") (pintype "power_in"))
      (node (ref "IC1") (pin "5") (pinfunction "VIN_5") (pintype "power_in"))
      (node (ref "IC8") (pin "1") (pinfunction "VIN_1") (pintype "power_in"))
      (node (ref "Q3") (pin "4") (pinfunction "S_4") (pintype "passive"))
      (node (ref "Q4") (pin "4") (pinfunction "S_4") (pintype "passive"))
      (node (ref "R11") (pin "2") (pinfunction "2_2") (pintype "passive"))
      (node (ref "R12") (pin "2") (pinfunction "2_2") (pintype "passive"))
      (node (ref "R42") (pin "1") (pinfunction "1_1") (pintype "passive"))
      (node (ref "R5") (pin "1") (pinfunction "1_1") (pintype "passive"))
      (node (ref "SJ1") (pin "1") (pinfunction "1_1") (pintype "passive"))
    )
    (net (code "3") (name "+9V") (class "Default")
      (node (ref "CONN1") (pin "A4") (pinfunction "+9V_A4") (pintype "power_in"))
      (node (ref "SJ1") (pin "3") (pinfunction "3_3") (pintype "passive"))
    )
    (net (code "4") (name "/+1V2") (class "Default")
      (node (ref "C12") (pin "1") (pinfunction "1_1") (pintype "passive"))
      (node (ref "C14") (pin "1") (pinfunction "1_1") (pintype "passive"))
      (node (ref "C18") (pin "1") (pinfunction "1_1") (pintype "passive"))
      (node (ref "C21") (pin "1") (pinfunction "1_1") (pintype "passive"))
      (node (ref "C22") (pin "1") (pinfunction "1_1") (pintype "passive"))
      (node (ref "C26") (pin "1") (pinfunction "1_1") (pintype "passive"))
      (node (ref "C28") (pin "1") (pinfunction "1_1") (pintype "passive"))
      (node (ref "C4") (pin "1") (pinfunction "1_1") (pintype "passive"))
      (node (ref "C45") (pin "2") (pinfunction "2_2") (pintype "passive"))
      (node (ref "C7") (pin "1") (pinfunction "1_1") (pintype "passive"))
      (node (ref "C9") (pin "1") (pinfunction "1_1") (pintype "passive"))
      (node (ref "IC2") (pin "102") (pinfunction "__VCCINT_6_102") (pintype "power_in"))
      (node (ref "IC2") (pin "109") (pinfunction "__VCCD_PLL2_109") (pintype "power_in"))
      (node (ref "IC2") (pin "116") (pinfunction "__VCCINT_7_116") (pintype "power_in"))
      (node (ref "IC2") (pin "134") (pinfunction "__VCCINT_8_134") (pintype "power_in"))
      (node (ref "IC2") (pin "29") (pinfunction "__VCCINT_2_29") (pintype "power_in"))
      (node (ref "IC2") (pin "37") (pinfunction "__VCCD_PLL1_37") (pintype "power_in"))
      (node (ref "IC2") (pin "45") (pinfunction "__VCCINT_3_45") (pintype "power_in"))
      (node (ref "IC2") (pin "5") (pinfunction "__VCCINT_1_5") (pintype "power_in"))
      (node (ref "IC2") (pin "61") (pinfunction "__VCCINT_4_61") (pintype "power_in"))
      (node (ref "IC2") (pin "78") (pinfunction "__VCCINT_5_78") (pintype "power_in"))
      (node (ref "L1") (pin "P$2") (pinfunction "2_P$2") (pintype "passive"))
      (node (ref "R19") (pin "2") (pinfunction "2_2") (pintype "passive"))
      (node (ref "TP1") (pin "TP") (pinfunction "TP_TP") (pintype "input"))
    )
    (net (code "5") (name "/+2V5") (class "Default")
      (node (ref "C27") (pin "1") (pinfunction "1_1") (pintype "passive"))
      (node (ref "C47") (pin "2") (pinfunction "2_2") (pintype "passive"))
      (node (ref "C8") (pin "1") (pinfunction "1_1") (pintype "passive"))
      (node (ref "IC2") (pin "107") (pinfunction "__VCCA2_107") (pintype "power_in"))
      (node (ref "IC2") (pin "35") (pinfunction "__VCCA1_35") (pintype "power_in"))
      (node (ref "IC8") (pin "5") (pinfunction "VOUT_5") (pintype "power_in"))
      (node (ref "TP3") (pin "TP") (pinfunction "TP_TP") (pintype "input"))
    )
    (net (code "6") (name "/+12V") (class "Default")
      (node (ref "CONN1") (pin "B22") (pinfunction "+12V_B22") (pintype "power_in"))
    )
    (net (code "7") (name "/-5V") (class "Default")
      (node (ref "CONN1") (pin "B20") (pinfunction "-5V_B20") (pintype "power_in"))
    )
    (net (code "8") (name "/-12V") (class "Default")
      (node (ref "CONN1") (pin "B23") (pinfunction "-12V_B23") (pintype "power_in"))
    )
    (net (code "9") (name "/A0") (class "Default")
      (node (ref "CONN1") (pin "A9") (pinfunction "A0_A9") (pintype "bidirectional"))
      (node (ref "RN4") (pin "1") (pinfunction "1_1") (pintype "passive"))
    )
    (net (code "10") (name "/A1") (class "Default")
      (node (ref "CONN1") (pin "A10") (pinfunction "A1_A10") (pintype "bidirectional"))
      (node (ref "RN4") (pin "2") (pinfunction "1_2") (pintype "passive"))
    )
    (net (code "11") (name "/A2") (class "Default")
      (node (ref "CONN1") (pin "A11") (pinfunction "A2_A11") (pintype "bidirectional"))
      (node (ref "RN4") (pin "3") (pinfunction "1_3") (pintype "passive"))
    )
    (net (code "12") (name "/A3") (class "Default")
      (node (ref "CONN1") (pin "A12") (pinfunction "A3_A12") (pintype "bidirectional"))
      (node (ref "RN4") (pin "4") (pinfunction "1_4") (pintype "passive"))
    )
    (net (code "13") (name "/A4") (class "Default")
      (node (ref "CONN1") (pin "A24") (pinfunction "A4_A24") (pintype "bidirectional"))
      (node (ref "RN5") (pin "4") (pinfunction "1_4") (pintype "passive"))
    )
    (net (code "14") (name "/A5") (class "Default")
      (node (ref "CONN1") (pin "A23") (pinfunction "A5_A23") (pintype "bidirectional"))
      (node (ref "RN5") (pin "3") (pinfunction "1_3") (pintype "passive"))
    )
    (net (code "15") (name "/A6") (class "Default")
      (node (ref "CONN1") (pin "A22") (pinfunction "A6_A22") (pintype "bidirectional"))
      (node (ref "RN5") (pin "2") (pinfunction "1_2") (pintype "passive"))
    )
    (net (code "16") (name "/A7") (class "Default")
      (node (ref "CONN1") (pin "A21") (pinfunction "A7_A21") (pintype "bidirectional"))
      (node (ref "RN5") (pin "1") (pinfunction "1_1") (pintype "passive"))
    )
    (net (code "17") (name "/A8") (class "Default")
      (node (ref "CONN1") (pin "B26") (pinfunction "A8_B26") (pintype "bidirectional"))
      (node (ref "RN6") (pin "1") (pinfunction "1_1") (pintype "passive"))
    )
    (net (code "18") (name "/A9") (class "Default")
      (node (ref "CONN1") (pin "A27") (pinfunction "A9_A27") (pintype "bidirectional"))
      (node (ref "RN6") (pin "2") (pinfunction "1_2") (pintype "passive"))
    )
    (net (code "19") (name "/A10") (class "Default")
      (node (ref "CONN1") (pin "B27") (pinfunction "A10_B27") (pintype "bidirectional"))
      (node (ref "RN6") (pin "3") (pinfunction "1_3") (pintype "passive"))
    )
    (net (code "20") (name "/A11") (class "Default")
      (node (ref "CONN1") (pin "A28") (pinfunction "A11_A28") (pintype "bidirectional"))
      (node (ref "RN6") (pin "4") (pinfunction "1_4") (pintype "passive"))
    )
    (net (code "21") (name "/A12") (class "Default")
      (node (ref "CONN1") (pin "A2") (pinfunction "A12_A2") (pintype "bidirectional"))
      (node (ref "RN3") (pin "4") (pinfunction "1_4") (pintype "passive"))
    )
    (net (code "22") (name "/A13") (class "Default")
      (node (ref "CONN1") (pin "B2") (pinfunction "A13_B2") (pintype "bidirectional"))
      (node (ref "RN3") (pin "3") (pinfunction "1_3") (pintype "passive"))
    )
    (net (code "23") (name "/A14") (class "Default")
      (node (ref "CONN1") (pin "A1") (pinfunction "A14_A1") (pintype "bidirectional"))
      (node (ref "RN3") (pin "2") (pinfunction "1_2") (pintype "passive"))
    )
    (net (code "24") (name "/A15") (class "Default")
      (node (ref "CONN1") (pin "B1") (pinfunction "A15_B1") (pintype "bidirectional"))
      (node (ref "RN3") (pin "1") (pinfunction "1_1") (pintype "passive"))
    )
    (net (code "25") (name "/A_BUS_OE") (class "Default")
      (node (ref "IC10") (pin "19") (pinfunction "G_19") (pintype "input"))
      (node (ref "IC11") (pin "19") (pinfunction "G_19") (pintype "input"))
      (node (ref "IC2") (pin "10") (pinfunction "__IO_7_10") (pintype "bidirectional"))
      (node (ref "R25") (pin "2") (pinfunction "2_2") (pintype "passive"))
    )
    (net (code "26") (name "/BLUE") (class "Default")
      (node (ref "R50") (pin "2") (pinfunction "2_2") (pintype "passive"))
      (node (ref "R55") (pin "2") (pinfunction "2_2") (pintype "passive"))
      (node (ref "R56") (pin "2") (pinfunction "2_2") (pintype "passive"))
      (node (ref "X1") (pin "3") (pinfunction "3_3") (pintype "passive"))
    )
    (net (code "27") (name "/BLUE0") (class "Default")
      (node (ref "R55") (pin "1") (pinfunction "1_1") (pintype "passive"))
      (node (ref "U$2") (pin "10") (pinfunction "10_10") (pintype "passive"))
    )
    (net (code "28") (name "/BLUE1") (class "Default")
      (node (ref "R56") (pin "1") (pinfunction "1_1") (pintype "passive"))
      (node (ref "U$2") (pin "9") (pinfunction "9_9") (pintype "passive"))
    )
    (net (code "29") (name "/CK") (class "Default")
      (node (ref "CONN1") (pin "A8") (pinfunction "CK_A8") (pintype "bidirectional"))
      (node (ref "RN1") (pin "1") (pinfunction "1_1") (pintype "passive"))
    )
    (net (code "30") (name "/CONF_DONE") (class "Default")
      (node (ref "IC2") (pin "92") (pinfunction "__CONF_DONE_92") (pintype "bidirectional"))
      (node (ref "R27") (pin "1") (pinfunction "1_1") (pintype "passive"))
      (node (ref "U1") (pin "7") (pinfunction "IO35_7") (pintype "input"))
    )
    (net (code "31") (name "/CTRL_OE") (class "Default")
      (node (ref "IC2") (pin "129") (pinfunction "__IO_74_129") (pintype "bidirectional"))
      (node (ref "IC3") (pin "19") (pinfunction "G_19") (pintype "input"))
      (node (ref "R26") (pin "2") (pinfunction "2_2") (pintype "passive"))
    )
    (net (code "32") (name "/D0") (class "Default")
      (node (ref "CONN1") (pin "B6") (pinfunction "D0_B6") (pintype "bidirectional"))
      (node (ref "RN7") (pin "2") (pinfunction "1_2") (pintype "passive"))
    )
    (net (code "33") (name "/D1") (class "Default")
      (node (ref "CONN1") (pin "B7") (pinfunction "D1_B7") (pintype "bidirectional"))
      (node (ref "RN7") (pin "3") (pinfunction "1_3") (pintype "passive"))
    )
    (net (code "34") (name "/D2") (class "Default")
      (node (ref "CONN1") (pin "B8") (pinfunction "D2_B8") (pintype "bidirectional"))
      (node (ref "RN7") (pin "4") (pinfunction "1_4") (pintype "passive"))
    )
    (net (code "35") (name "/D3") (class "Default")
      (node (ref "CONN1") (pin "B11") (pinfunction "D3_B11") (pintype "bidirectional"))
      (node (ref "RN8") (pin "3") (pinfunction "1_3") (pintype "passive"))
    )
    (net (code "36") (name "/D4") (class "Default")
      (node (ref "CONN1") (pin "B12") (pinfunction "D4_B12") (pintype "bidirectional"))
      (node (ref "RN8") (pin "4") (pinfunction "1_4") (pintype "passive"))
    )
    (net (code "37") (name "/D5") (class "Default")
      (node (ref "CONN1") (pin "B10") (pinfunction "D5_B10") (pintype "bidirectional"))
      (node (ref "RN8") (pin "2") (pinfunction "1_2") (pintype "passive"))
    )
    (net (code "38") (name "/D6") (class "Default")
      (node (ref "CONN1") (pin "B9") (pinfunction "D6_B9") (pintype "bidirectional"))
      (node (ref "RN8") (pin "1") (pinfunction "1_1") (pintype "passive"))
    )
    (net (code "39") (name "/D7") (class "Default")
      (node (ref "CONN1") (pin "B3") (pinfunction "D7_B3") (pintype "bidirectional"))
      (node (ref "RN7") (pin "1") (pinfunction "1_1") (pintype "passive"))
    )
    (net (code "40") (name "/DM") (class "Default")
      (node (ref "R36") (pin "2") (pinfunction "2_2") (pintype "passive"))
      (node (ref "TV26") (pin "3") (pinfunction "B_3") (pintype "bidirectional"))
      (node (ref "USB2") (pin "D-") (pinfunction "D-_D-") (pintype "bidirectional"))
    )
    (net (code "41") (name "/DP") (class "Default")
      (node (ref "R35") (pin "2") (pinfunction "2_2") (pintype "passive"))
      (node (ref "R43") (pin "2") (pinfunction "2_2") (pintype "passive"))
      (node (ref "TV26") (pin "2") (pinfunction "A_2") (pintype "bidirectional"))
      (node (ref "USB2") (pin "D+") (pinfunction "D+_D+") (pintype "bidirectional"))
    )
    (net (code "42") (name "/D_BUS_DIR") (class "Default")
      (node (ref "IC2") (pin "11") (pinfunction "__IO_8_11") (pintype "bidirectional"))
      (node (ref "IC4") (pin "1") (pinfunction "DIR_1") (pintype "input"))
    )
    (net (code "43") (name "/D_BUS_OE") (class "Default")
      (node (ref "IC2") (pin "7") (pinfunction "__IO_5_7") (pintype "bidirectional"))
      (node (ref "IC4") (pin "19") (pinfunction "G_19") (pintype "input"))
      (node (ref "R24") (pin "2") (pinfunction "2_2") (pintype "passive"))
    )
    (net (code "44") (name "/ESP_EN") (class "Default")
      (node (ref "C1") (pin "2") (pinfunction "2_2") (pintype "passive"))
      (node (ref "R2") (pin "1") (pinfunction "1_1") (pintype "passive"))
      (node (ref "S1") (pin "B2") (pinfunction "2_B2") (pintype "passive"))
      (node (ref "U1") (pin "3") (pinfunction "EN_3") (pintype "bidirectional"))
    )
    (net (code "45") (name "/ESP_IO0") (class "Default")
      (node (ref "C2") (pin "2") (pinfunction "2_2") (pintype "passive"))
      (node (ref "R3") (pin "1") (pinfunction "1_1") (pintype "passive"))
      (node (ref "S2") (pin "B2") (pinfunction "2_B2") (pintype "passive"))
      (node (ref "U1") (pin "25") (pinfunction "IO0_25") (pintype "bidirectional"))
    )
    (net (code "46") (name "/ESP_IO26") (class "Default")
      (node (ref "IC2") (pin "138") (pinfunction "__IO_80_138") (pintype "bidirectional"))
      (node (ref "U1") (pin "11") (pinfunction "IO26_11") (pintype "bidirectional"))
    )
    (net (code "47") (name "/ESP_IO27") (class "Default")
      (node (ref "IC2") (pin "141") (pinfunction "__IO_81_141") (pintype "bidirectional"))
      (node (ref "U1") (pin "12") (pinfunction "IO27_12") (pintype "bidirectional"))
    )
    (net (code "48") (name "/ESP_MISO") (class "Default")
      (node (ref "IC2") (pin "6") (pinfunction "__IO_4/DATA/ADSO_6") (pintype "bidirectional"))
      (node (ref "U1") (pin "31") (pinfunction "IO19_31") (pintype "bidirectional"))
    )
    (net (code "49") (name "/ESP_MOSI") (class "Default")
      (node (ref "IC2") (pin "13") (pinfunction "__DATA0_13") (pintype "bidirectional"))
      (node (ref "U1") (pin "37") (pinfunction "IO23_37") (pintype "bidirectional"))
    )
    (net (code "50") (name "/ESP_NCS0") (class "Default")
      (node (ref "IC2") (pin "3") (pinfunction "__IO_3_3") (pintype "bidirectional"))
      (node (ref "U1") (pin "29") (pinfunction "IO5_29") (pintype "bidirectional"))
    )
    (net (code "51") (name "/ESP_QDH") (class "Default")
      (node (ref "IC2") (pin "1") (pinfunction "__IO_1_1") (pintype "bidirectional"))
      (node (ref "U1") (pin "33") (pinfunction "IO21_33") (pintype "bidirectional"))
    )
    (net (code "52") (name "/ESP_QWP") (class "Default")
      (node (ref "IC2") (pin "143") (pinfunction "__IO_83_143") (pintype "bidirectional"))
      (node (ref "U1") (pin "36") (pinfunction "IO22_36") (pintype "bidirectional"))
    )
    (net (code "53") (name "/ESP_RX") (class "Default")
      (node (ref "IC7") (pin "6") (pinfunction "TX_6") (pintype "output"))
      (node (ref "U1") (pin "34") (pinfunction "RXD0_34") (pintype "bidirectional"))
    )
    (net (code "54") (name "/ESP_SCK") (class "Default")
      (node (ref "IC2") (pin "12") (pinfunction "__DCLK_12") (pintype "input"))
      (node (ref "IC2") (pin "23") (pinfunction "__CLK1_23") (pintype "input"))
      (node (ref "U1") (pin "30") (pinfunction "IO18_30") (pintype "bidirectional"))
    )
    (net (code "55") (name "/ESP_TX") (class "Default")
      (node (ref "IC7") (pin "7") (pinfunction "RX_7") (pintype "input"))
      (node (ref "U1") (pin "35") (pinfunction "TXD0_35") (pintype "bidirectional"))
    )
    (net (code "56") (name "/EXT0") (class "Default")
      (node (ref "IC2") (pin "135") (pinfunction "__IO_77_135") (pintype "bidirectional"))
      (node (ref "U$7") (pin "3") (pinfunction "3_3") (pintype "passive"))
    )
    (net (code "57") (name "/EXT1") (class "Default")
      (node (ref "IC2") (pin "133") (pinfunction "__IO_76_133") (pintype "bidirectional"))
      (node (ref "U$7") (pin "4") (pinfunction "4_4") (pintype "passive"))
    )
    (net (code "58") (name "/EXT2") (class "Default")
      (node (ref "IC2") (pin "128") (pinfunction "__IO_73_128") (pintype "bidirectional"))
      (node (ref "U$7") (pin "5") (pinfunction "5_5") (pintype "passive"))
    )
    (net (code "59") (name "/EXT3") (class "Default")
      (node (ref "IC2") (pin "127") (pinfunction "__IO_72_127") (pintype "bidirectional"))
      (node (ref "U$7") (pin "6") (pinfunction "6_6") (pintype "passive"))
    )
    (net (code "60") (name "/EXT4") (class "Default")
      (node (ref "IC2") (pin "126") (pinfunction "__IO_71_126") (pintype "bidirectional"))
      (node (ref "U$7") (pin "7") (pinfunction "7_7") (pintype "passive"))
    )
    (net (code "61") (name "/EXT5") (class "Default")
      (node (ref "IC2") (pin "125") (pinfunction "__IO_70_125") (pintype "bidirectional"))
      (node (ref "U$7") (pin "8") (pinfunction "8_8") (pintype "passive"))
    )
    (net (code "62") (name "/EXT6") (class "Default")
      (node (ref "IC2") (pin "124") (pinfunction "__IO_69_124") (pintype "bidirectional"))
      (node (ref "U$7") (pin "9") (pinfunction "9_9") (pintype "passive"))
    )
    (net (code "63") (name "/EXT7") (class "Default")
      (node (ref "IC2") (pin "121") (pinfunction "__IO_68_121") (pintype "bidirectional"))
      (node (ref "U$7") (pin "10") (pinfunction "10_10") (pintype "passive"))
    )
    (net (code "64") (name "/FLED0") (class "Default")
      (node (ref "IC2") (pin "76") (pinfunction "__IO_44_76") (pintype "bidirectional"))
      (node (ref "R41") (pin "2") (pinfunction "2_2") (pintype "passive"))
    )
    (net (code "65") (name "/FLED1") (class "Default")
      (node (ref "IC2") (pin "77") (pinfunction "__IO_45_77") (pintype "bidirectional"))
      (node (ref "R40") (pin "2") (pinfunction "2_2") (pintype "passive"))
    )
    (net (code "66") (name "/FLED2") (class "Default")
      (node (ref "IC2") (pin "80") (pinfunction "__IO_46_80") (pintype "bidirectional"))
      (node (ref "R39") (pin "2") (pinfunction "2_2") (pintype "passive"))
    )
    (net (code "67") (name "/FORCE_INT") (class "Default")
      (node (ref "IC2") (pin "53") (pinfunction "__IO_26_53") (pintype "bidirectional"))
      (node (ref "Q2") (pin "1") (pinfunction "G_1") (pintype "passive"))
    )
    (net (code "68") (name "/FORCE_IORQULA") (class "Default")
      (node (ref "IC2") (pin "136") (pinfunction "__IO_78_136") (pintype "bidirectional"))
      (node (ref "Q4") (pin "2") (pinfunction "G_2") (pintype "passive"))
    )
    (net (code "69") (name "/FORCE_NMI") (class "Default")
      (node (ref "IC2") (pin "137") (pinfunction "__IO_79_137") (pintype "bidirectional"))
      (node (ref "Q6") (pin "1") (pinfunction "G_1") (pintype "passive"))
    )
    (net (code "70") (name "/FORCE_RESET") (class "Default")
      (node (ref "IC2") (pin "67") (pinfunction "__IO_35_67") (pintype "bidirectional"))
      (node (ref "Q1") (pin "1") (pinfunction "G_1") (pintype "passive"))
    )
    (net (code "71") (name "/FORCE_ROMCS") (class "Default")
      (node (ref "IC2") (pin "132") (pinfunction "__IO_75_132") (pintype "bidirectional"))
      (node (ref "Q3") (pin "2") (pinfunction "G_2") (pintype "passive"))
    )
    (net (code "72") (name "/FR1") (class "Default")
      (node (ref "Q3") (pin "5") (pinfunction "G_5") (pintype "passive"))
      (node (ref "Q3") (pin "6") (pinfunction "D_6") (pintype "passive"))
      (node (ref "R5") (pin "2") (pinfunction "2_2") (pintype "passive"))
    )
    (net (code "73") (name "/FR2") (class "Default")
      (node (ref "Q4") (pin "5") (pinfunction "G_5") (pintype "passive"))
      (node (ref "Q4") (pin "6") (pinfunction "D_6") (pintype "passive"))
      (node (ref "R42") (pin "2") (pinfunction "2_2") (pintype "passive"))
    )
    (net (code "74") (name "/GREEN") (class "Default")
      (node (ref "R49") (pin "2") (pinfunction "2_2") (pintype "passive"))
      (node (ref "R53") (pin "2") (pinfunction "2_2") (pintype "passive"))
      (node (ref "R54") (pin "2") (pinfunction "2_2") (pintype "passive"))
      (node (ref "X1") (pin "2") (pinfunction "2_2") (pintype "passive"))
    )
    (net (code "75") (name "/GREEN0") (class "Default")
      (node (ref "R53") (pin "1") (pinfunction "1_1") (pintype "passive"))
      (node (ref "U$2") (pin "8") (pinfunction "8_8") (pintype "passive"))
    )
    (net (code "76") (name "/GREEN1") (class "Default")
      (node (ref "R54") (pin "1") (pinfunction "1_1") (pintype "passive"))
      (node (ref "U$2") (pin "7") (pinfunction "7_7") (pintype "passive"))
    )
    (net (code "77") (name "/HSYNC") (class "Default")
      (node (ref "R47") (pin "1") (pinfunction "1_1") (pintype "passive"))
      (node (ref "U$2") (pin "3") (pinfunction "3_3") (pintype "passive"))
    )
    (net (code "78") (name "/INT") (class "Default")
      (node (ref "CONN1") (pin "B13") (pinfunction "INT_B13") (pintype "bidirectional"))
      (node (ref "Q2") (pin "3") (pinfunction "D_3") (pintype "passive"))
      (node (ref "RN1") (pin "2") (pinfunction "1_2") (pintype "passive"))
    )
    (net (code "79") (name "/IORQ") (class "Default")
      (node (ref "CONN1") (pin "B17") (pinfunction "IORQ_B17") (pintype "bidirectional"))
      (node (ref "RN1") (pin "4") (pinfunction "1_4") (pintype "passive"))
    )
    (net (code "80") (name "/IORQULA") (class "Default")
      (node (ref "CONN1") (pin "A13") (pinfunction "IORQULA_A13") (pintype "bidirectional"))
      (node (ref "Q4") (pin "3") (pinfunction "D_3") (pintype "passive"))
    )
    (net (code "81") (name "/LED1") (class "Default")
      (node (ref "R21") (pin "2") (pinfunction "2_2") (pintype "passive"))
      (node (ref "U1") (pin "8") (pinfunction "IO32_8") (pintype "bidirectional"))
    )
    (net (code "82") (name "/LED2") (class "Default")
      (node (ref "IC2") (pin "2") (pinfunction "__IO_2_2") (pintype "bidirectional"))
      (node (ref "R22") (pin "2") (pinfunction "2_2") (pintype "passive"))
    )
    (net (code "83") (name "/M1") (class "Default")
      (node (ref "CONN1") (pin "B24") (pinfunction "M1_B24") (pintype "bidirectional"))
      (node (ref "RN2") (pin "3") (pinfunction "1_3") (pintype "passive"))
    )
    (net (code "84") (name "/MREQ") (class "Default")
      (node (ref "CONN1") (pin "B16") (pinfunction "MREQ_B16") (pintype "bidirectional"))
      (node (ref "RN1") (pin "3") (pinfunction "1_3") (pintype "passive"))
    )
    (net (code "85") (name "/NCONFIG") (class "Default")
      (node (ref "IC2") (pin "14") (pinfunction "__NCONFIG_14") (pintype "bidirectional"))
      (node (ref "R7") (pin "1") (pinfunction "1_1") (pintype "passive"))
      (node (ref "U1") (pin "10") (pinfunction "IO25_10") (pintype "bidirectional"))
    )
    (net (code "86") (name "/NMI") (class "Default")
      (node (ref "CONN1") (pin "B14") (pinfunction "NMI_B14") (pintype "bidirectional"))
      (node (ref "Q6") (pin "3") (pinfunction "D_3") (pintype "passive"))
    )
    (net (code "87") (name "/NSTATUS") (class "Default")
      (node (ref "IC2") (pin "9") (pinfunction "__NSTATUS_9") (pintype "bidirectional"))
      (node (ref "R6") (pin "1") (pinfunction "1_1") (pintype "passive"))
      (node (ref "U1") (pin "27") (pinfunction "IO16_27") (pintype "bidirectional"))
    )
    (net (code "88") (name "/PEN1") (class "Default")
      (node (ref "IC1") (pin "4") (pinfunction "NEN_4") (pintype "input"))
      (node (ref "R37") (pin "1") (pinfunction "1_1") (pintype "passive"))
    )
    (net (code "89") (name "/PULLUP_EN") (class "Default")
      (node (ref "Q5") (pin "1") (pinfunction "G_1") (pintype "passive"))
      (node (ref "R28") (pin "2") (pinfunction "2_2") (pintype "passive"))
      (node (ref "U1") (pin "9") (pinfunction "IO33_9") (pintype "bidirectional"))
    )
    (net (code "90") (name "/RAMCLK") (class "Default")
      (node (ref "IC12") (pin "6") (pinfunction "SCK_6") (pintype "input"))
      (node (ref "IC2") (pin "84") (pinfunction "__IO_48_84") (pintype "bidirectional"))
      (node (ref "IC9") (pin "6") (pinfunction "SCK_6") (pintype "input"))
    )
    (net (code "91") (name "/RAMD0") (class "Default")
      (node (ref "IC2") (pin "99") (pinfunction "__IO_53_99") (pintype "bidirectional"))
      (node (ref "IC9") (pin "5") (pinfunction "SI/SIO[0]_5") (pintype "bidirectional"))
    )
    (net (code "92") (name "/RAMD1") (class "Default")
      (node (ref "IC2") (pin "98") (pinfunction "__IO_52_98") (pintype "bidirectional"))
      (node (ref "IC9") (pin "2") (pinfunction "SO/SIO[1]_2") (pintype "bidirectional"))
    )
    (net (code "93") (name "/RAMD2") (class "Default")
      (node (ref "IC2") (pin "87") (pinfunction "__IO_51_87") (pintype "bidirectional"))
      (node (ref "IC9") (pin "3") (pinfunction "SIO[2]_3") (pintype "bidirectional"))
    )
    (net (code "94") (name "/RAMD3") (class "Default")
      (node (ref "IC2") (pin "100") (pinfunction "__IO_54_100") (pintype "bidirectional"))
      (node (ref "IC9") (pin "7") (pinfunction "SIO[3]_7") (pintype "bidirectional"))
    )
    (net (code "95") (name "/RAMD4") (class "Default")
      (node (ref "IC12") (pin "5") (pinfunction "SI/SIO[0]_5") (pintype "bidirectional"))
      (node (ref "IC2") (pin "83") (pinfunction "__IO_47_83") (pintype "bidirectional"))
    )
    (net (code "96") (name "/RAMD5") (class "Default")
      (node (ref "IC12") (pin "2") (pinfunction "SO/SIO[1]_2") (pintype "bidirectional"))
      (node (ref "IC2") (pin "101") (pinfunction "__IO_55_101") (pintype "bidirectional"))
    )
    (net (code "97") (name "/RAMD6") (class "Default")
      (node (ref "IC12") (pin "3") (pinfunction "SIO[2]_3") (pintype "bidirectional"))
      (node (ref "IC2") (pin "86") (pinfunction "__IO_50_86") (pintype "bidirectional"))
    )
    (net (code "98") (name "/RAMD7") (class "Default")
      (node (ref "IC12") (pin "7") (pinfunction "SIO[3]_7") (pintype "bidirectional"))
      (node (ref "IC2") (pin "85") (pinfunction "__IO_49_85") (pintype "bidirectional"))
    )
    (net (code "99") (name "/RAMNCS") (class "Default")
      (node (ref "IC12") (pin "1") (pinfunction "NCS_1") (pintype "input"))
      (node (ref "IC2") (pin "103") (pinfunction "__IO_56_103") (pintype "bidirectional"))
      (node (ref "IC9") (pin "1") (pinfunction "NCS_1") (pintype "input"))
    )
    (net (code "100") (name "/RCV") (class "Default")
      (node (ref "IC2") (pin "106") (pinfunction "__IO_59_106") (pintype "bidirectional"))
      (node (ref "U3") (pin "4") (pinfunction "RCV_4") (pintype "output"))
    )
    (net (code "101") (name "/RD") (class "Default")
      (node (ref "CONN1") (pin "B18") (pinfunction "RD_B18") (pintype "bidirectional"))
      (node (ref "RN2") (pin "1") (pinfunction "1_1") (pintype "passive"))
    )
    (net (code "102") (name "/RED") (class "Default")
      (node (ref "R48") (pin "2") (pinfunction "2_2") (pintype "passive"))
      (node (ref "R51") (pin "2") (pinfunction "2_2") (pintype "passive"))
      (node (ref "R52") (pin "2") (pinfunction "2_2") (pintype "passive"))
      (node (ref "X1") (pin "1") (pinfunction "1_1") (pintype "passive"))
    )
    (net (code "103") (name "/RED0") (class "Default")
      (node (ref "R51") (pin "1") (pinfunction "1_1") (pintype "passive"))
      (node (ref "U$2") (pin "6") (pinfunction "6_6") (pintype "passive"))
    )
    (net (code "104") (name "/RED1") (class "Default")
      (node (ref "R52") (pin "1") (pinfunction "1_1") (pintype "passive"))
      (node (ref "U$2") (pin "5") (pinfunction "5_5") (pintype "passive"))
    )
    (net (code "105") (name "/RESET") (class "Default")
      (node (ref "CONN1") (pin "A20") (pinfunction "RESET_A20") (pintype "bidirectional"))
      (node (ref "Q1") (pin "3") (pinfunction "D_3") (pintype "passive"))
    )
    (net (code "106") (name "/RFSH") (class "Default")
      (node (ref "CONN1") (pin "B25") (pinfunction "RFSH_B25") (pintype "bidirectional"))
      (node (ref "RN2") (pin "4") (pinfunction "1_4") (pintype "passive"))
    )
    (net (code "107") (name "/ROMCS") (class "Default")
      (node (ref "CONN1") (pin "A25") (pinfunction "ROMCS_A25") (pintype "bidirectional"))
      (node (ref "Q3") (pin "3") (pinfunction "D_3") (pintype "passive"))
    )
    (net (code "108") (name "/SDMMC_CK") (class "Default")
      (node (ref "R32") (pin "1") (pinfunction "1_1") (pintype "passive"))
      (node (ref "SD1") (pin "5") (pinfunction "CLK(SCLK)_5") (pintype "input"))
      (node (ref "U1") (pin "13") (pinfunction "IO14_13") (pintype "bidirectional"))
    )
    (net (code "109") (name "/SDMMC_CMD") (class "Default")
      (node (ref "R31") (pin "1") (pinfunction "1_1") (pintype "passive"))
      (node (ref "SD1") (pin "3") (pinfunction "CMD(DI)_3") (pintype "bidirectional"))
      (node (ref "U1") (pin "23") (pinfunction "IO15_23") (pintype "bidirectional"))
    )
    (net (code "110") (name "/SDMMC_D0") (class "Default")
      (node (ref "R33") (pin "1") (pinfunction "1_1") (pintype "passive"))
      (node (ref "SD1") (pin "7") (pinfunction "DAT0(DO)_7") (pintype "bidirectional"))
      (node (ref "U1") (pin "24") (pinfunction "IO2_24") (pintype "bidirectional"))
    )
    (net (code "111") (name "/SDMMC_D1") (class "Default")
      (node (ref "R34") (pin "1") (pinfunction "1_1") (pintype "passive"))
      (node (ref "SD1") (pin "8") (pinfunction "DAT1_8") (pintype "bidirectional"))
      (node (ref "U1") (pin "26") (pinfunction "IO4_26") (pintype "bidirectional"))
    )
    (net (code "112") (name "/SDMMC_D2") (class "Default")
      (node (ref "R29") (pin "2") (pinfunction "2_2") (pintype "passive"))
      (node (ref "SD1") (pin "1") (pinfunction "DAT2_1") (pintype "bidirectional"))
      (node (ref "U1") (pin "14") (pinfunction "IO12_14") (pintype "bidirectional"))
    )
    (net (code "113") (name "/SDMMC_D3") (class "Default")
      (node (ref "R30") (pin "1") (pinfunction "1_1") (pintype "passive"))
      (node (ref "SD1") (pin "2") (pinfunction "CD/DAT3(~{CS})_2") (pintype "bidirectional"))
      (node (ref "U1") (pin "16") (pinfunction "IO13_16") (pintype "bidirectional"))
    )
    (net (code "114") (name "/SDMMC_DET") (class "Default")
      (node (ref "R1") (pin "2") (pinfunction "2_2") (pintype "passive"))
      (node (ref "SD1") (pin "A") (pinfunction "A_A") (pintype "passive"))
      (node (ref "U1") (pin "28") (pinfunction "IO17_28") (pintype "bidirectional"))
    )
    (net (code "115") (name "/SOFTCON") (class "Default")
      (node (ref "IC2") (pin "111") (pinfunction "__IO_61_111") (pintype "bidirectional"))
      (node (ref "U3") (pin "2") (pinfunction "SOFTCON_2") (pintype "input"))
    )
    (net (code "116") (name "/SPEED") (class "Default")
      (node (ref "IC2") (pin "112") (pinfunction "__IO_62_112") (pintype "bidirectional"))
      (node (ref "U3") (pin "10") (pinfunction "SPEED_10") (pintype "input"))
    )
    (net (code "117") (name "/SW1") (class "Default")
      (node (ref "C42") (pin "1") (pinfunction "1_1") (pintype "passive"))
      (node (ref "IC5") (pin "3") (pinfunction "SW_3") (pintype "passive"))
      (node (ref "L1") (pin "P$1") (pinfunction "1_P$1") (pintype "passive"))
    )
    (net (code "118") (name "/SW2") (class "Default")
      (node (ref "C43") (pin "1") (pinfunction "1_1") (pintype "passive"))
      (node (ref "IC6") (pin "3") (pinfunction "SW_3") (pintype "passive"))
      (node (ref "L2") (pin "P$1") (pinfunction "1_P$1") (pintype "passive"))
    )
    (net (code "119") (name "/SWITCH") (class "Default")
      (node (ref "R4") (pin "1") (pinfunction "1_1") (pintype "passive"))
      (node (ref "S3") (pin "B2") (pinfunction "2_B2") (pintype "passive"))
      (node (ref "U1") (pin "6") (pinfunction "IO34_6") (pintype "input"))
    )
    (net (code "120") (name "/TCK") (class "Default")
      (node (ref "CONN2") (pin "1") (pinfunction "1_1") (pintype "passive"))
      (node (ref "IC2") (pin "16") (pinfunction "__TCK_16") (pintype "bidirectional"))
      (node (ref "R10") (pin "1") (pinfunction "1_1") (pintype "passive"))
    )
    (net (code "121") (name "/TDI") (class "Default")
      (node (ref "CONN2") (pin "9") (pinfunction "9_9") (pintype "passive"))
      (node (ref "IC2") (pin "15") (pinfunction "__TDI_15") (pintype "bidirectional"))
    )
    (net (code "122") (name "/TDO") (class "Default")
      (node (ref "CONN2") (pin "3") (pinfunction "3_3") (pintype "passive"))
      (node (ref "IC2") (pin "20") (pinfunction "__TDO_20") (pintype "bidirectional"))
      (node (ref "R8") (pin "1") (pinfunction "1_1") (pintype "passive"))
    )
    (net (code "123") (name "/TMS") (class "Default")
      (node (ref "CONN2") (pin "5") (pinfunction "5_5") (pintype "passive"))
      (node (ref "IC2") (pin "18") (pinfunction "__TMS_18") (pintype "bidirectional"))
      (node (ref "R9") (pin "1") (pinfunction "1_1") (pintype "passive"))
    )
    (net (code "124") (name "/USB_FLT") (class "Default")
      (node (ref "IC1") (pin "3") (pinfunction "FAULT_3") (pintype "output"))
      (node (ref "IC2") (pin "115") (pinfunction "__IO_65_115") (pintype "bidirectional"))
      (node (ref "R38") (pin "1") (pinfunction "1_1") (pintype "passive"))
    )
    (net (code "125") (name "/USB_OE") (class "Default")
      (node (ref "IC2") (pin "110") (pinfunction "__IO_60_110") (pintype "bidirectional"))
      (node (ref "U3") (pin "3") (pinfunction "~{OE}_3") (pintype "input"))
    )
    (net (code "126") (name "/USB_PWREN") (class "Default")
      (node (ref "IC2") (pin "119") (pinfunction "__IO_66_119") (pintype "bidirectional"))
      (node (ref "R37") (pin "2") (pinfunction "2_2") (pintype "passive"))
    )
    (net (code "127") (name "/VBUS") (class "Default")
      (node (ref "C59") (pin "+") (pinfunction "+_+") (pintype "passive"))
      (node (ref "IC1") (pin "1") (pinfunction "VOUT_1") (pintype "power_in"))
      (node (ref "TV26") (pin "4") (pinfunction "C_4") (pintype "bidirectional"))
      (node (ref "USB2") (pin "VBUS") (pinfunction "VBUS_VBUS") (pintype "bidirectional"))
    )
    (net (code "128") (name "/VM") (class "Default")
      (node (ref "IC2") (pin "104") (pinfunction "__IO_57_104") (pintype "bidirectional"))
      (node (ref "U3") (pin "6") (pinfunction "VM_6") (pintype "output"))
    )
    (net (code "129") (name "/VMO") (class "Default")
      (node (ref "IC2") (pin "114") (pinfunction "__IO_64_114") (pintype "bidirectional"))
      (node (ref "U3") (pin "14") (pinfunction "VMO_14") (pintype "input"))
    )
    (net (code "130") (name "/VP") (class "Default")
      (node (ref "IC2") (pin "105") (pinfunction "__IO_58_105") (pintype "bidirectional"))
      (node (ref "U3") (pin "5") (pinfunction "VP_5") (pintype "output"))
    )
    (net (code "131") (name "/VPO") (class "Default")
      (node (ref "IC2") (pin "113") (pinfunction "__IO_63_113") (pintype "bidirectional"))
      (node (ref "U3") (pin "13") (pinfunction "VPO_13") (pintype "input"))
    )
    (net (code "132") (name "/VPU") (class "Default")
      (node (ref "R43") (pin "1") (pinfunction "1_1") (pintype "passive"))
      (node (ref "U3") (pin "1") (pinfunction "VPU(3.3)_1") (pintype "power_in"))
    )
    (net (code "133") (name "/VREG") (class "Default")
      (node (ref "C31") (pin "2") (pinfunction "2_2") (pintype "passive"))
      (node (ref "C32") (pin "2") (pinfunction "2_2") (pintype "passive"))
      (node (ref "C33") (pin "2") (pinfunction "2_2") (pintype "passive"))
      (node (ref "C34") (pin "2") (pinfunction "2_2") (pintype "passive"))
      (node (ref "IC5") (pin "2") (pinfunction "IN_2") (pintype "power_in"))
      (node (ref "IC6") (pin "2") (pinfunction "IN_2") (pintype "power_in"))
      (node (ref "SJ1") (pin "2") (pinfunction "2_2") (pintype "passive"))
    )
    (net (code "134") (name "/VSYNC") (class "Default")
      (node (ref "R46") (pin "1") (pinfunction "1_1") (pintype "passive"))
      (node (ref "U$2") (pin "4") (pinfunction "4_4") (pintype "passive"))
    )
    (net (code "135") (name "/WR") (class "Default")
      (node (ref "CONN1") (pin "B19") (pinfunction "WR_B19") (pintype "bidirectional"))
      (node (ref "RN2") (pin "2") (pinfunction "1_2") (pintype "passive"))
    )
    (net (code "136") (name "/XCK") (class "Default")
      (node (ref "IC2") (pin "54") (pinfunction "__IO_27_54") (pintype "bidirectional"))
      (node (ref "IC3") (pin "18") (pinfunction "B1_18") (pintype "bidirectional"))
    )
    (net (code "137") (name "/XD0") (class "Default")
      (node (ref "IC2") (pin "43") (pinfunction "__IO_19_43") (pintype "bidirectional"))
      (node (ref "IC4") (pin "17") (pinfunction "B2_17") (pintype "bidirectional"))
    )
    (net (code "138") (name "/XD1") (class "Default")
      (node (ref "IC2") (pin "44") (pinfunction "__IO_20_44") (pintype "bidirectional"))
      (node (ref "IC4") (pin "16") (pinfunction "B3_16") (pintype "bidirectional"))
    )
    (net (code "139") (name "/XD2") (class "Default")
      (node (ref "IC2") (pin "46") (pinfunction "__IO_21_46") (pintype "bidirectional"))
      (node (ref "IC4") (pin "15") (pinfunction "B4_15") (pintype "bidirectional"))
    )
    (net (code "140") (name "/XD3") (class "Default")
      (node (ref "IC2") (pin "51") (pinfunction "__IO_24_51") (pintype "bidirectional"))
      (node (ref "IC4") (pin "12") (pinfunction "B7_12") (pintype "bidirectional"))
    )
    (net (code "141") (name "/XD4") (class "Default")
      (node (ref "IC2") (pin "52") (pinfunction "__IO_25_52") (pintype "bidirectional"))
      (node (ref "IC4") (pin "11") (pinfunction "B8_11") (pintype "bidirectional"))
    )
    (net (code "142") (name "/XD5") (class "Default")
      (node (ref "IC2") (pin "50") (pinfunction "__IO_23_50") (pintype "bidirectional"))
      (node (ref "IC4") (pin "13") (pinfunction "B6_13") (pintype "bidirectional"))
    )
    (net (code "143") (name "/XD6") (class "Default")
      (node (ref "IC2") (pin "49") (pinfunction "__IO_22_49") (pintype "bidirectional"))
      (node (ref "IC4") (pin "14") (pinfunction "B5_14") (pintype "bidirectional"))
    )
    (net (code "144") (name "/XD7") (class "Default")
      (node (ref "IC2") (pin "42") (pinfunction "__IO_18_42") (pintype "bidirectional"))
      (node (ref "IC4") (pin "18") (pinfunction "B1_18") (pintype "bidirectional"))
    )
    (net (code "145") (name "/XINT") (class "Default")
      (node (ref "IC2") (pin "55") (pinfunction "__IO_28_55") (pintype "bidirectional"))
      (node (ref "IC3") (pin "17") (pinfunction "B2_17") (pintype "bidirectional"))
    )
    (net (code "146") (name "/XIORQ") (class "Default")
      (node (ref "IC2") (pin "59") (pinfunction "__IO_30_59") (pintype "bidirectional"))
      (node (ref "IC3") (pin "15") (pinfunction "B4_15") (pintype "bidirectional"))
    )
    (net (code "147") (name "/XM1") (class "Default")
      (node (ref "IC2") (pin "65") (pinfunction "__IO_33_65") (pintype "bidirectional"))
      (node (ref "IC3") (pin "12") (pinfunction "B7_12") (pintype "bidirectional"))
    )
    (net (code "148") (name "/XMREQ") (class "Default")
      (node (ref "IC2") (pin "58") (pinfunction "__IO_29_58") (pintype "bidirectional"))
      (node (ref "IC3") (pin "16") (pinfunction "B3_16") (pintype "bidirectional"))
    )
    (net (code "149") (name "/XRD") (class "Default")
      (node (ref "IC2") (pin "60") (pinfunction "__IO_31_60") (pintype "bidirectional"))
      (node (ref "IC3") (pin "14") (pinfunction "B5_14") (pintype "bidirectional"))
    )
    (net (code "150") (name "/XRFSH") (class "Default")
      (node (ref "IC2") (pin "66") (pinfunction "__IO_34_66") (pintype "bidirectional"))
      (node (ref "IC3") (pin "11") (pinfunction "B8_11") (pintype "bidirectional"))
    )
    (net (code "151") (name "/XWR") (class "Default")
      (node (ref "IC2") (pin "64") (pinfunction "__IO_32_64") (pintype "bidirectional"))
      (node (ref "IC3") (pin "13") (pinfunction "B6_13") (pintype "bidirectional"))
    )
    (net (code "152") (name "/ZX_A0") (class "Default")
      (node (ref "IC10") (pin "14") (pinfunction "B5_14") (pintype "bidirectional"))
      (node (ref "IC2") (pin "33") (pinfunction "__IO_14_33") (pintype "bidirectional"))
    )
    (net (code "153") (name "/ZX_A1") (class "Default")
      (node (ref "IC10") (pin "13") (pinfunction "B6_13") (pintype "bidirectional"))
      (node (ref "IC2") (pin "34") (pinfunction "__IO_15_34") (pintype "bidirectional"))
    )
    (net (code "154") (name "/ZX_A2") (class "Default")
      (node (ref "IC10") (pin "12") (pinfunction "B7_12") (pintype "bidirectional"))
      (node (ref "IC2") (pin "38") (pinfunction "__IO_16_38") (pintype "bidirectional"))
    )
    (net (code "155") (name "/ZX_A3") (class "Default")
      (node (ref "IC10") (pin "11") (pinfunction "B8_11") (pintype "bidirectional"))
      (node (ref "IC2") (pin "39") (pinfunction "__IO_17_39") (pintype "bidirectional"))
    )
    (net (code "156") (name "/ZX_A4") (class "Default")
      (node (ref "IC11") (pin "15") (pinfunction "B4_15") (pintype "bidirectional"))
      (node (ref "IC2") (pin "71") (pinfunction "__IO_39_71") (pintype "bidirectional"))
    )
    (net (code "157") (name "/ZX_A5") (class "Default")
      (node (ref "IC11") (pin "16") (pinfunction "B3_16") (pintype "bidirectional"))
      (node (ref "IC2") (pin "70") (pinfunction "__IO_38_70") (pintype "bidirectional"))
    )
    (net (code "158") (name "/ZX_A6") (class "Default")
      (node (ref "IC11") (pin "17") (pinfunction "B2_17") (pintype "bidirectional"))
      (node (ref "IC2") (pin "69") (pinfunction "__IO_37_69") (pintype "bidirectional"))
    )
    (net (code "159") (name "/ZX_A7") (class "Default")
      (node (ref "IC11") (pin "18") (pinfunction "B1_18") (pintype "bidirectional"))
      (node (ref "IC2") (pin "68") (pinfunction "__IO_36_68") (pintype "bidirectional"))
    )
    (net (code "160") (name "/ZX_A8") (class "Default")
      (node (ref "IC11") (pin "14") (pinfunction "B5_14") (pintype "bidirectional"))
      (node (ref "IC2") (pin "72") (pinfunction "__IO_40_72") (pintype "bidirectional"))
    )
    (net (code "161") (name "/ZX_A9") (class "Default")
      (node (ref "IC11") (pin "13") (pinfunction "B6_13") (pintype "bidirectional"))
      (node (ref "IC2") (pin "73") (pinfunction "__IO_41_73") (pintype "bidirectional"))
    )
    (net (code "162") (name "/ZX_A10") (class "Default")
      (node (ref "IC11") (pin "12") (pinfunction "B7_12") (pintype "bidirectional"))
      (node (ref "IC2") (pin "74") (pinfunction "__IO_42_74") (pintype "bidirectional"))
    )
    (net (code "163") (name "/ZX_A11") (class "Default")
      (node (ref "IC11") (pin "11") (pinfunction "B8_11") (pintype "bidirectional"))
      (node (ref "IC2") (pin "75") (pinfunction "__IO_43_75") (pintype "bidirectional"))
    )
    (net (code "164") (name "/ZX_A12") (class "Default")
      (node (ref "IC10") (pin "15") (pinfunction "B4_15") (pintype "bidirectional"))
      (node (ref "IC2") (pin "32") (pinfunction "__IO_13_32") (pintype "bidirectional"))
    )
    (net (code "165") (name "/ZX_A13") (class "Default")
      (node (ref "IC10") (pin "16") (pinfunction "B3_16") (pintype "bidirectional"))
      (node (ref "IC2") (pin "31") (pinfunction "__IO_12_31") (pintype "bidirectional"))
    )
    (net (code "166") (name "/ZX_A14") (class "Default")
      (node (ref "IC10") (pin "17") (pinfunction "B2_17") (pintype "bidirectional"))
      (node (ref "IC2") (pin "30") (pinfunction "__IO_11_30") (pintype "bidirectional"))
    )
    (net (code "167") (name "/ZX_A15") (class "Default")
      (node (ref "IC10") (pin "18") (pinfunction "B1_18") (pintype "bidirectional"))
      (node (ref "IC2") (pin "28") (pinfunction "__IO_10_28") (pintype "bidirectional"))
    )
    (net (code "168") (name "GND") (class "Default")
      (node (ref "C1") (pin "1") (pinfunction "1_1") (pintype "passive"))
      (node (ref "C10") (pin "2") (pinfunction "2_2") (pintype "passive"))
      (node (ref "C11") (pin "2") (pinfunction "2_2") (pintype "passive"))
      (node (ref "C12") (pin "2") (pinfunction "2_2") (pintype "passive"))
      (node (ref "C13") (pin "2") (pinfunction "2_2") (pintype "passive"))
      (node (ref "C14") (pin "2") (pinfunction "2_2") (pintype "passive"))
      (node (ref "C15") (pin "2") (pinfunction "2_2") (pintype "passive"))
      (node (ref "C16") (pin "2") (pinfunction "2_2") (pintype "passive"))
      (node (ref "C17") (pin "2") (pinfunction "2_2") (pintype "passive"))
      (node (ref "C18") (pin "2") (pinfunction "2_2") (pintype "passive"))
      (node (ref "C19") (pin "2") (pinfunction "2_2") (pintype "passive"))
      (node (ref "C2") (pin "1") (pinfunction "1_1") (pintype "passive"))
      (node (ref "C20") (pin "2") (pinfunction "2_2") (pintype "passive"))
      (node (ref "C21") (pin "2") (pinfunction "2_2") (pintype "passive"))
      (node (ref "C22") (pin "2") (pinfunction "2_2") (pintype "passive"))
      (node (ref "C23") (pin "2") (pinfunction "2_2") (pintype "passive"))
      (node (ref "C24") (pin "2") (pinfunction "2_2") (pintype "passive"))
      (node (ref "C25") (pin "2") (pinfunction "2_2") (pintype "passive"))
      (node (ref "C26") (pin "2") (pinfunction "2_2") (pintype "passive"))
      (node (ref "C27") (pin "2") (pinfunction "2_2") (pintype "passive"))
      (node (ref "C28") (pin "2") (pinfunction "2_2") (pintype "passive"))
      (node (ref "C29") (pin "2") (pinfunction "2_2") (pintype "passive"))
      (node (ref "C3") (pin "2") (pinfunction "2_2") (pintype "passive"))
      (node (ref "C30") (pin "2") (pinfunction "2_2") (pintype "passive"))
      (node (ref "C31") (pin "1") (pinfunction "1_1") (pintype "passive"))
      (node (ref "C32") (pin "1") (pinfunction "1_1") (pintype "passive"))
      (node (ref "C33") (pin "1") (pinfunction "1_1") (pintype "passive"))
      (node (ref "C34") (pin "1") (pinfunction "1_1") (pintype "passive"))
      (node (ref "C35") (pin "1") (pinfunction "1_1") (pintype "passive"))
      (node (ref "C36") (pin "1") (pinfunction "1_1") (pintype "passive"))
      (node (ref "C37") (pin "2") (pinfunction "2_2") (pintype "passive"))
      (node (ref "C38") (pin "1") (pinfunction "1_1") (pintype "passive"))
      (node (ref "C39") (pin "1") (pinfunction "1_1") (pintype "passive"))
      (node (ref "C4") (pin "2") (pinfunction "2_2") (pintype "passive"))
      (node (ref "C40") (pin "2") (pinfunction "2_2") (pintype "passive"))
      (node (ref "C41") (pin "2") (pinfunction "2_2") (pintype "passive"))
      (node (ref "C45") (pin "1") (pinfunction "1_1") (pintype "passive"))
      (node (ref "C46") (pin "1") (pinfunction "1_1") (pintype "passive"))
      (node (ref "C47") (pin "1") (pinfunction "1_1") (pintype "passive"))
      (node (ref "C48") (pin "1") (pinfunction "1_1") (pintype "passive"))
      (node (ref "C49") (pin "1") (pinfunction "1_1") (pintype "passive"))
      (node (ref "C5") (pin "2") (pinfunction "2_2") (pintype "passive"))
      (node (ref "C50") (pin "2") (pinfunction "2_2") (pintype "passive"))
      (node (ref "C51") (pin "2") (pinfunction "2_2") (pintype "passive"))
      (node (ref "C52") (pin "2") (pinfunction "2_2") (pintype "passive"))
      (node (ref "C53") (pin "2") (pinfunction "2_2") (pintype "passive"))
      (node (ref "C56") (pin "2") (pinfunction "2_2") (pintype "passive"))
      (node (ref "C57") (pin "MINUS") (pinfunction "-_MINUS") (pintype "passive"))
      (node (ref "C58") (pin "1") (pinfunction "1_1") (pintype "passive"))
      (node (ref "C59") (pin "-") (pinfunction "-_-") (pintype "passive"))
      (node (ref "C6") (pin "2") (pinfunction "2_2") (pintype "passive"))
      (node (ref "C60") (pin "MINUS") (pinfunction "-_MINUS") (pintype "passive"))
      (node (ref "C7") (pin "2") (pinfunction "2_2") (pintype "passive"))
      (node (ref "C8") (pin "2") (pinfunction "2_2") (pintype "passive"))
      (node (ref "C9") (pin "2") (pinfunction "2_2") (pintype "passive"))
      (node (ref "CONN1") (pin "A14") (pinfunction "GND_A14") (pintype "power_in"))
      (node (ref "CONN1") (pin "A6") (pinfunction "GND_A6") (pintype "power_in"))
      (node (ref "CONN1") (pin "A7") (pinfunction "GND_A7") (pintype "power_in"))
      (node (ref "CONN2") (pin "10") (pinfunction "10_10") (pintype "passive"))
      (node (ref "CONN2") (pin "2") (pinfunction "2_2") (pintype "passive"))
      (node (ref "IC1") (pin "2") (pinfunction "GND_2") (pintype "power_in"))
      (node (ref "IC10") (pin "10") (pinfunction "GND_10") (pintype "power_in"))
      (node (ref "IC11") (pin "10") (pinfunction "GND_10") (pintype "power_in"))
      (node (ref "IC12") (pin "4") (pinfunction "GND_4") (pintype "power_in"))
      (node (ref "IC2") (pin "108") (pinfunction "__GNDA2_108") (pintype "power_in"))
      (node (ref "IC2") (pin "118") (pinfunction "__GND_12_118") (pintype "power_in"))
      (node (ref "IC2") (pin "123") (pinfunction "__GND_13_123") (pintype "power_in"))
      (node (ref "IC2") (pin "131") (pinfunction "__GND_14_131") (pintype "power_in"))
      (node (ref "IC2") (pin "140") (pinfunction "__GND_15_140") (pintype "power_in"))
      (node (ref "IC2") (pin "145") (pinfunction "TP_145") (pintype "bidirectional"))
      (node (ref "IC2") (pin "19") (pinfunction "__GND_2_19") (pintype "power_in"))
      (node (ref "IC2") (pin "21") (pinfunction "__NCE_21") (pintype "bidirectional"))
      (node (ref "IC2") (pin "22") (pinfunction "__GND_3_22") (pintype "power_in"))
      (node (ref "IC2") (pin "27") (pinfunction "__GND_4_27") (pintype "power_in"))
      (node (ref "IC2") (pin "36") (pinfunction "__GNDA1_36") (pintype "power_in"))
      (node (ref "IC2") (pin "4") (pinfunction "__GND_1_4") (pintype "power_in"))
      (node (ref "IC2") (pin "41") (pinfunction "__GND_5_41") (pintype "power_in"))
      (node (ref "IC2") (pin "48") (pinfunction "__GND_6_48") (pintype "power_in"))
      (node (ref "IC2") (pin "57") (pinfunction "__GND_7_57") (pintype "power_in"))
      (node (ref "IC2") (pin "63") (pinfunction "__GND_8_63") (pintype "power_in"))
      (node (ref "IC2") (pin "79") (pinfunction "__GND_9_79") (pintype "power_in"))
      (node (ref "IC2") (pin "82") (pinfunction "__GND_10_82") (pintype "power_in"))
      (node (ref "IC2") (pin "94") (pinfunction "__MSEL0_94") (pintype "bidirectional"))
      (node (ref "IC2") (pin "95") (pinfunction "__GND_11_95") (pintype "power_in"))
      (node (ref "IC2") (pin "96") (pinfunction "__MSEL1_96") (pintype "bidirectional"))
      (node (ref "IC3") (pin "10") (pinfunction "GND_10") (pintype "power_in"))
      (node (ref "IC4") (pin "10") (pinfunction "GND_10") (pintype "power_in"))
      (node (ref "IC5") (pin "4") (pinfunction "GND_4") (pintype "power_in"))
      (node (ref "IC6") (pin "4") (pinfunction "GND_4") (pintype "power_in"))
      (node (ref "IC7") (pin "3") (pinfunction "GND_3") (pintype "power_in"))
      (node (ref "IC8") (pin "2") (pinfunction "GND_2") (pintype "power_in"))
      (node (ref "IC9") (pin "4") (pinfunction "GND_4") (pintype "power_in"))
      (node (ref "Q1") (pin "2") (pinfunction "S_2") (pintype "passive"))
      (node (ref "Q2") (pin "2") (pinfunction "S_2") (pintype "passive"))
      (node (ref "Q3") (pin "1") (pinfunction "S_1") (pintype "passive"))
      (node (ref "Q4") (pin "1") (pinfunction "S_1") (pintype "passive"))
      (node (ref "Q6") (pin "2") (pinfunction "S_2") (pintype "passive"))
      (node (ref "R10") (pin "2") (pinfunction "2_2") (pintype "passive"))
      (node (ref "R17") (pin "1") (pinfunction "1_1") (pintype "passive"))
      (node (ref "R18") (pin "1") (pinfunction "1_1") (pintype "passive"))
      (node (ref "R23") (pin "2") (pinfunction "2_2") (pintype "passive"))
      (node (ref "R44") (pin "1") (pinfunction "1_1") (pintype "passive"))
      (node (ref "R45") (pin "2") (pinfunction "2_2") (pintype "passive"))
      (node (ref "R48") (pin "1") (pinfunction "1_1") (pintype "passive"))
      (node (ref "R49") (pin "1") (pinfunction "1_1") (pintype "passive"))
      (node (ref "R50") (pin "1") (pinfunction "1_1") (pintype "passive"))
      (node (ref "S1") (pin "A2") (pinfunction "1_A2") (pintype "passive"))
      (node (ref "S2") (pin "A2") (pinfunction "1_A2") (pintype "passive"))
      (node (ref "S3") (pin "A2") (pinfunction "1_A2") (pintype "passive"))
      (node (ref "SD1") (pin "6") (pinfunction "VSS_6") (pintype "power_in"))
      (node (ref "SD1") (pin "B") (pinfunction "B_B") (pintype "passive"))
      (node (ref "SD1") (pin "MNT1") (pinfunction "S1_MNT1") (pintype "passive"))
      (node (ref "SD1") (pin "MNT2") (pinfunction "S2_MNT2") (pintype "passive"))
      (node (ref "SD1") (pin "MNT3") (pinfunction "S3_MNT3") (pintype "passive"))
      (node (ref "SD1") (pin "MNT4") (pinfunction "S4_MNT4") (pintype "passive"))
      (node (ref "TV26") (pin "1") (pinfunction "COM_1") (pintype "bidirectional"))
      (node (ref "U$1") (pin "2") (pinfunction "GND_2") (pintype "power_in"))
      (node (ref "U$2") (pin "2") (pinfunction "2_2") (pintype "passive"))
      (node (ref "U$7") (pin "2") (pinfunction "2_2") (pintype "passive"))
      (node (ref "U1") (pin "1") (pinfunction "GND_1") (pintype "bidirectional"))
      (node (ref "U1") (pin "15") (pinfunction "GND_15") (pintype "bidirectional"))
      (node (ref "U1") (pin "38") (pinfunction "GND_38") (pintype "bidirectional"))
      (node (ref "U1") (pin "GND") (pinfunction "GND_GND") (pintype "bidirectional"))
      (node (ref "U3") (pin "8") (pinfunction "GND_8") (pintype "passive"))
      (node (ref "USB1") (pin "P5") (pinfunction "GND_P5") (pintype "bidirectional"))
      (node (ref "USB2") (pin "GND") (pinfunction "GND_GND") (pintype "bidirectional"))
      (node (ref "X1") (pin "10") (pinfunction "10_10") (pintype "passive"))
      (node (ref "X1") (pin "5") (pinfunction "5_5") (pintype "passive"))
      (node (ref "X1") (pin "6") (pinfunction "6_6") (pintype "passive"))
      (node (ref "X1") (pin "7") (pinfunction "7_7") (pintype "passive"))
      (node (ref "X1") (pin "8") (pinfunction "8_8") (pintype "passive"))
    )
    (net (code "169") (name "Net-(C42-Pad2)") (class "Default")
      (node (ref "C42") (pin "2") (pinfunction "2_2") (pintype "passive"))
      (node (ref "R13") (pin "1") (pinfunction "1_1") (pintype "passive"))
    )
    (net (code "170") (name "Net-(C43-Pad2)") (class "Default")
      (node (ref "C43") (pin "2") (pinfunction "2_2") (pintype "passive"))
      (node (ref "R14") (pin "1") (pinfunction "1_1") (pintype "passive"))
    )
    (net (code "171") (name "Net-(C44-Pad1)") (class "Default")
      (node (ref "C44") (pin "1") (pinfunction "1_1") (pintype "passive"))
      (node (ref "R16") (pin "2") (pinfunction "2_2") (pintype "passive"))
      (node (ref "R18") (pin "2") (pinfunction "2_2") (pintype "passive"))
      (node (ref "R20") (pin "1") (pinfunction "1_1") (pintype "passive"))
    )
    (net (code "172") (name "Net-(IC2-__CLK2)") (class "Default")
      (node (ref "IC2") (pin "24") (pinfunction "__CLK2_24") (pintype "input"))
      (node (ref "U$1") (pin "3") (pinfunction "FO_3") (pintype "output"))
    )
    (net (code "173") (name "Net-(IC2-__IO_6{slash}FLASH_NCS{slash}NCSO)") (class "Default")
      (node (ref "IC2") (pin "8") (pinfunction "__IO_6/FLASH_NCS/NCSO_8") (pintype "bidirectional"))
      (node (ref "TP4") (pin "TP") (pinfunction "TP_TP") (pintype "input"))
    )
    (net (code "174") (name "Net-(IC2-__IO_84)") (class "Default")
      (node (ref "IC2") (pin "144") (pinfunction "__IO_84_144") (pintype "bidirectional"))
      (node (ref "TP5") (pin "TP") (pinfunction "TP_TP") (pintype "input"))
    )
    (net (code "175") (name "Net-(IC3A-A1)") (class "Default")
      (node (ref "IC3") (pin "2") (pinfunction "A1_2") (pintype "bidirectional"))
      (node (ref "RN1") (pin "8") (pinfunction "2_8") (pintype "passive"))
    )
    (net (code "176") (name "Net-(IC3A-A2)") (class "Default")
      (node (ref "IC3") (pin "3") (pinfunction "A2_3") (pintype "bidirectional"))
      (node (ref "RN1") (pin "7") (pinfunction "2_7") (pintype "passive"))
    )
    (net (code "177") (name "Net-(IC3A-A3)") (class "Default")
      (node (ref "IC3") (pin "4") (pinfunction "A3_4") (pintype "bidirectional"))
      (node (ref "RN1") (pin "6") (pinfunction "2_6") (pintype "passive"))
    )
    (net (code "178") (name "Net-(IC3A-A4)") (class "Default")
      (node (ref "IC3") (pin "5") (pinfunction "A4_5") (pintype "bidirectional"))
      (node (ref "RN1") (pin "5") (pinfunction "2_5") (pintype "passive"))
    )
    (net (code "179") (name "Net-(IC3A-A5)") (class "Default")
      (node (ref "IC3") (pin "6") (pinfunction "A5_6") (pintype "bidirectional"))
      (node (ref "RN2") (pin "8") (pinfunction "2_8") (pintype "passive"))
    )
    (net (code "180") (name "Net-(IC3A-A6)") (class "Default")
      (node (ref "IC3") (pin "7") (pinfunction "A6_7") (pintype "bidirectional"))
      (node (ref "RN2") (pin "7") (pinfunction "2_7") (pintype "passive"))
    )
    (net (code "181") (name "Net-(IC3A-A7)") (class "Default")
      (node (ref "IC3") (pin "8") (pinfunction "A7_8") (pintype "bidirectional"))
      (node (ref "RN2") (pin "6") (pinfunction "2_6") (pintype "passive"))
    )
    (net (code "182") (name "Net-(IC3A-A8)") (class "Default")
      (node (ref "IC3") (pin "9") (pinfunction "A8_9") (pintype "bidirectional"))
      (node (ref "RN2") (pin "5") (pinfunction "2_5") (pintype "passive"))
    )
    (net (code "183") (name "Net-(IC4A-A1)") (class "Default")
      (node (ref "IC4") (pin "2") (pinfunction "A1_2") (pintype "bidirectional"))
      (node (ref "RN7") (pin "8") (pinfunction "2_8") (pintype "passive"))
    )
    (net (code "184") (name "Net-(IC4A-A2)") (class "Default")
      (node (ref "IC4") (pin "3") (pinfunction "A2_3") (pintype "bidirectional"))
      (node (ref "RN7") (pin "7") (pinfunction "2_7") (pintype "passive"))
    )
    (net (code "185") (name "Net-(IC4A-A3)") (class "Default")
      (node (ref "IC4") (pin "4") (pinfunction "A3_4") (pintype "bidirectional"))
      (node (ref "RN7") (pin "6") (pinfunction "2_6") (pintype "passive"))
    )
    (net (code "186") (name "Net-(IC4A-A4)") (class "Default")
      (node (ref "IC4") (pin "5") (pinfunction "A4_5") (pintype "bidirectional"))
      (node (ref "RN7") (pin "5") (pinfunction "2_5") (pintype "passive"))
    )
    (net (code "187") (name "Net-(IC4A-A5)") (class "Default")
      (node (ref "IC4") (pin "6") (pinfunction "A5_6") (pintype "bidirectional"))
      (node (ref "RN8") (pin "8") (pinfunction "2_8") (pintype "passive"))
    )
    (net (code "188") (name "Net-(IC4A-A6)") (class "Default")
      (node (ref "IC4") (pin "7") (pinfunction "A6_7") (pintype "bidirectional"))
      (node (ref "RN8") (pin "7") (pinfunction "2_7") (pintype "passive"))
    )
    (net (code "189") (name "Net-(IC4A-A7)") (class "Default")
      (node (ref "IC4") (pin "8") (pinfunction "A7_8") (pintype "bidirectional"))
      (node (ref "RN8") (pin "6") (pinfunction "2_6") (pintype "passive"))
    )
    (net (code "190") (name "Net-(IC4A-A8)") (class "Default")
      (node (ref "IC4") (pin "9") (pinfunction "A8_9") (pintype "bidirectional"))
      (node (ref "RN8") (pin "5") (pinfunction "2_5") (pintype "passive"))
    )
    (net (code "191") (name "Net-(IC5-BST)") (class "Default")
      (node (ref "IC5") (pin "5") (pinfunction "BST_5") (pintype "passive"))
      (node (ref "R13") (pin "2") (pinfunction "2_2") (pintype "passive"))
    )
    (net (code "192") (name "Net-(IC5-EN)") (class "Default")
      (node (ref "IC5") (pin "6") (pinfunction "EN_6") (pintype "input"))
      (node (ref "R11") (pin "1") (pinfunction "1_1") (pintype "passive"))
    )
    (net (code "193") (name "Net-(IC5-FB)") (class "Default")
      (node (ref "IC5") (pin "8") (pinfunction "FB_8") (pintype "passive"))
      (node (ref "R15") (pin "1") (pinfunction "1_1") (pintype "passive"))
    )
    (net (code "194") (name "Net-(IC5-SS)") (class "Default")
      (node (ref "C38") (pin "2") (pinfunction "2_2") (pintype "passive"))
      (node (ref "IC5") (pin "1") (pinfunction "SS_1") (pintype "passive"))
    )
    (net (code "195") (name "Net-(IC5-VCC)") (class "Default")
      (node (ref "C35") (pin "2") (pinfunction "2_2") (pintype "passive"))
      (node (ref "IC5") (pin "7") (pinfunction "VCC_7") (pintype "passive"))
    )
    (net (code "196") (name "Net-(IC6-BST)") (class "Default")
      (node (ref "IC6") (pin "5") (pinfunction "BST_5") (pintype "passive"))
      (node (ref "R14") (pin "2") (pinfunction "2_2") (pintype "passive"))
    )
    (net (code "197") (name "Net-(IC6-EN)") (class "Default")
      (node (ref "C58") (pin "2") (pinfunction "2_2") (pintype "passive"))
      (node (ref "IC6") (pin "6") (pinfunction "EN_6") (pintype "input"))
      (node (ref "R12") (pin "1") (pinfunction "1_1") (pintype "passive"))
    )
    (net (code "198") (name "Net-(IC6-FB)") (class "Default")
      (node (ref "IC6") (pin "8") (pinfunction "FB_8") (pintype "passive"))
      (node (ref "R16") (pin "1") (pinfunction "1_1") (pintype "passive"))
    )
    (net (code "199") (name "Net-(IC6-SS)") (class "Default")
      (node (ref "C39") (pin "2") (pinfunction "2_2") (pintype "passive"))
      (node (ref "IC6") (pin "1") (pinfunction "SS_1") (pintype "passive"))
    )
    (net (code "200") (name "Net-(IC6-VCC)") (class "Default")
      (node (ref "C36") (pin "2") (pinfunction "2_2") (pintype "passive"))
      (node (ref "IC6") (pin "7") (pinfunction "VCC_7") (pintype "passive"))
    )
    (net (code "201") (name "Net-(IC7-DM)") (class "Default")
      (node (ref "IC7") (pin "2") (pinfunction "DM_2") (pintype "passive"))
      (node (ref "USB1") (pin "P2") (pinfunction "D-_P2") (pintype "bidirectional"))
    )
    (net (code "202") (name "Net-(IC7-DP)") (class "Default")
      (node (ref "IC7") (pin "1") (pinfunction "DP_1") (pintype "passive"))
      (node (ref "USB1") (pin "P3") (pinfunction "D+_P3") (pintype "bidirectional"))
    )
    (net (code "203") (name "Net-(IC10A-A1)") (class "Default")
      (node (ref "IC10") (pin "2") (pinfunction "A1_2") (pintype "bidirectional"))
      (node (ref "RN3") (pin "8") (pinfunction "2_8") (pintype "passive"))
    )
    (net (code "204") (name "Net-(IC10A-A2)") (class "Default")
      (node (ref "IC10") (pin "3") (pinfunction "A2_3") (pintype "bidirectional"))
      (node (ref "RN3") (pin "7") (pinfunction "2_7") (pintype "passive"))
    )
    (net (code "205") (name "Net-(IC10A-A3)") (class "Default")
      (node (ref "IC10") (pin "4") (pinfunction "A3_4") (pintype "bidirectional"))
      (node (ref "RN3") (pin "6") (pinfunction "2_6") (pintype "passive"))
    )
    (net (code "206") (name "Net-(IC10A-A4)") (class "Default")
      (node (ref "IC10") (pin "5") (pinfunction "A4_5") (pintype "bidirectional"))
      (node (ref "RN3") (pin "5") (pinfunction "2_5") (pintype "passive"))
    )
    (net (code "207") (name "Net-(IC10A-A5)") (class "Default")
      (node (ref "IC10") (pin "6") (pinfunction "A5_6") (pintype "bidirectional"))
      (node (ref "RN4") (pin "8") (pinfunction "2_8") (pintype "passive"))
    )
    (net (code "208") (name "Net-(IC10A-A6)") (class "Default")
      (node (ref "IC10") (pin "7") (pinfunction "A6_7") (pintype "bidirectional"))
      (node (ref "RN4") (pin "7") (pinfunction "2_7") (pintype "passive"))
    )
    (net (code "209") (name "Net-(IC10A-A7)") (class "Default")
      (node (ref "IC10") (pin "8") (pinfunction "A7_8") (pintype "bidirectional"))
      (node (ref "RN4") (pin "6") (pinfunction "2_6") (pintype "passive"))
    )
    (net (code "210") (name "Net-(IC10A-A8)") (class "Default")
      (node (ref "IC10") (pin "9") (pinfunction "A8_9") (pintype "bidirectional"))
      (node (ref "RN4") (pin "5") (pinfunction "2_5") (pintype "passive"))
    )
    (net (code "211") (name "Net-(IC11A-A1)") (class "Default")
      (node (ref "IC11") (pin "2") (pinfunction "A1_2") (pintype "bidirectional"))
      (node (ref "RN5") (pin "8") (pinfunction "2_8") (pintype "passive"))
    )
    (net (code "212") (name "Net-(IC11A-A2)") (class "Default")
      (node (ref "IC11") (pin "3") (pinfunction "A2_3") (pintype "bidirectional"))
      (node (ref "RN5") (pin "7") (pinfunction "2_7") (pintype "passive"))
    )
    (net (code "213") (name "Net-(IC11A-A3)") (class "Default")
      (node (ref "IC11") (pin "4") (pinfunction "A3_4") (pintype "bidirectional"))
      (node (ref "RN5") (pin "6") (pinfunction "2_6") (pintype "passive"))
    )
    (net (code "214") (name "Net-(IC11A-A4)") (class "Default")
      (node (ref "IC11") (pin "5") (pinfunction "A4_5") (pintype "bidirectional"))
      (node (ref "RN5") (pin "5") (pinfunction "2_5") (pintype "passive"))
    )
    (net (code "215") (name "Net-(IC11A-A5)") (class "Default")
      (node (ref "IC11") (pin "6") (pinfunction "A5_6") (pintype "bidirectional"))
      (node (ref "RN6") (pin "8") (pinfunction "2_8") (pintype "passive"))
    )
    (net (code "216") (name "Net-(IC11A-A6)") (class "Default")
      (node (ref "IC11") (pin "7") (pinfunction "A6_7") (pintype "bidirectional"))
      (node (ref "RN6") (pin "7") (pinfunction "2_7") (pintype "passive"))
    )
    (net (code "217") (name "Net-(IC11A-A7)") (class "Default")
      (node (ref "IC11") (pin "8") (pinfunction "A7_8") (pintype "bidirectional"))
      (node (ref "RN6") (pin "6") (pinfunction "2_6") (pintype "passive"))
    )
    (net (code "218") (name "Net-(IC11A-A8)") (class "Default")
      (node (ref "IC11") (pin "9") (pinfunction "A8_9") (pintype "bidirectional"))
      (node (ref "RN6") (pin "5") (pinfunction "2_5") (pintype "passive"))
    )
    (net (code "219") (name "Net-(LED1-PadC)") (class "Default")
      (node (ref "LED1") (pin "C") (pinfunction "C_C") (pintype "passive"))
      (node (ref "R21") (pin "1") (pinfunction "1_1") (pintype "passive"))
    )
    (net (code "220") (name "Net-(LED2-PadC)") (class "Default")
      (node (ref "LED2") (pin "C") (pinfunction "C_C") (pintype "passive"))
      (node (ref "R22") (pin "1") (pinfunction "1_1") (pintype "passive"))
    )
    (net (code "221") (name "Net-(LED3-PadC)") (class "Default")
      (node (ref "LED3") (pin "C") (pinfunction "C_C") (pintype "passive"))
      (node (ref "R23") (pin "1") (pinfunction "1_1") (pintype "passive"))
    )
    (net (code "222") (name "Net-(LED4-PadC)") (class "Default")
      (node (ref "LED4") (pin "C") (pinfunction "C_C") (pintype "passive"))
      (node (ref "R39") (pin "1") (pinfunction "1_1") (pintype "passive"))
    )
    (net (code "223") (name "Net-(LED5-PadC)") (class "Default")
      (node (ref "LED5") (pin "C") (pinfunction "C_C") (pintype "passive"))
      (node (ref "R40") (pin "1") (pinfunction "1_1") (pintype "passive"))
    )
    (net (code "224") (name "Net-(LED6-PadC)") (class "Default")
      (node (ref "LED6") (pin "C") (pinfunction "C_C") (pintype "passive"))
      (node (ref "R41") (pin "1") (pinfunction "1_1") (pintype "passive"))
    )
    (net (code "225") (name "Net-(Q5-D)") (class "Default")
      (node (ref "Q5") (pin "3") (pinfunction "D_3") (pintype "passive"))
      (node (ref "R29") (pin "1") (pinfunction "1_1") (pintype "passive"))
    )
    (net (code "226") (name "Net-(R15-Pad2)") (class "Default")
      (node (ref "R15") (pin "2") (pinfunction "2_2") (pintype "passive"))
      (node (ref "R17") (pin "2") (pinfunction "2_2") (pintype "passive"))
      (node (ref "R19") (pin "1") (pinfunction "1_1") (pintype "passive"))
    )
    (net (code "227") (name "Net-(R46-Pad2)") (class "Default")
      (node (ref "R46") (pin "2") (pinfunction "2_2") (pintype "passive"))
      (node (ref "X1") (pin "14") (pinfunction "14_14") (pintype "passive"))
    )
    (net (code "228") (name "Net-(R47-Pad2)") (class "Default")
      (node (ref "R47") (pin "2") (pinfunction "2_2") (pintype "passive"))
      (node (ref "X1") (pin "13") (pinfunction "13_13") (pintype "passive"))
    )
    (net (code "229") (name "Net-(U3-D+)") (class "Default")
      (node (ref "R35") (pin "1") (pinfunction "1_1") (pintype "passive"))
      (node (ref "U3") (pin "12") (pinfunction "D+_12") (pintype "bidirectional"))
    )
    (net (code "230") (name "Net-(U3-D-)") (class "Default")
      (node (ref "R36") (pin "1") (pinfunction "1_1") (pintype "passive"))
      (node (ref "U3") (pin "11") (pinfunction "D-_11") (pintype "bidirectional"))
    )
    (net (code "231") (name "Net-(U3-SUSPND)") (class "Default")
      (node (ref "R44") (pin "2") (pinfunction "2_2") (pintype "passive"))
      (node (ref "U3") (pin "7") (pinfunction "SUSPND_7") (pintype "input"))
    )
    (net (code "232") (name "PE") (class "Default")
      (node (ref "C50") (pin "1") (pinfunction "1_1") (pintype "passive"))
      (node (ref "R45") (pin "1") (pinfunction "1_1") (pintype "passive"))
      (node (ref "USB2") (pin "P$5") (pinfunction "SHIELD_P$5") (pintype "passive"))
      (node (ref "USB2") (pin "P$6") (pinfunction "SHIELD_P$6") (pintype "passive"))
    )
    (net (code "233") (name "unconnected-(CONN1-BUSACK-PadA26)") (class "Default")
      (node (ref "CONN1") (pin "A26") (pinfunction "BUSACK_A26") (pintype "bidirectional"))
    )
    (net (code "234") (name "unconnected-(CONN1-BUSREQ-PadA19)") (class "Default")
      (node (ref "CONN1") (pin "A19") (pinfunction "BUSREQ_A19") (pintype "bidirectional"))
    )
    (net (code "235") (name "unconnected-(CONN1-HALT-PadB15)") (class "Default")
      (node (ref "CONN1") (pin "B15") (pinfunction "HALT_B15") (pintype "bidirectional"))
    )
    (net (code "236") (name "unconnected-(CONN1-NC-PadB28)") (class "Default")
      (node (ref "CONN1") (pin "B28") (pinfunction "NC_B28") (pintype "bidirectional"))
    )
    (net (code "237") (name "unconnected-(CONN1-NC3-PadB4)") (class "Default")
      (node (ref "CONN1") (pin "B4") (pinfunction "NC3_B4") (pintype "passive"))
    )
    (net (code "238") (name "unconnected-(CONN1-U-PadA18)") (class "Default")
      (node (ref "CONN1") (pin "A18") (pinfunction "U_A18") (pintype "bidirectional"))
    )
    (net (code "239") (name "unconnected-(CONN1-V-PadA17)") (class "Default")
      (node (ref "CONN1") (pin "A17") (pinfunction "V_A17") (pintype "bidirectional"))
    )
    (net (code "240") (name "unconnected-(CONN1-VIDEO-PadA15)") (class "Default")
      (node (ref "CONN1") (pin "A15") (pinfunction "VIDEO_A15") (pintype "bidirectional"))
    )
    (net (code "241") (name "unconnected-(CONN1-WAIT-PadB21)") (class "Default")
      (node (ref "CONN1") (pin "B21") (pinfunction "WAIT_B21") (pintype "bidirectional"))
    )
    (net (code "242") (name "unconnected-(CONN1-YL-PadA16)") (class "Default")
      (node (ref "CONN1") (pin "A16") (pinfunction "YL_A16") (pintype "bidirectional"))
    )
    (net (code "243") (name "unconnected-(CONN2-Pad6)") (class "Default")
      (node (ref "CONN2") (pin "6") (pinfunction "6_6") (pintype "passive"))
    )
    (net (code "244") (name "unconnected-(CONN2-Pad7)") (class "Default")
      (node (ref "CONN2") (pin "7") (pinfunction "7_7") (pintype "passive"))
    )
    (net (code "245") (name "unconnected-(CONN2-Pad8)") (class "Default")
      (node (ref "CONN2") (pin "8") (pinfunction "8_8") (pintype "passive"))
    )
    (net (code "246") (name "unconnected-(IC2-__CLK3-Pad25)") (class "Default")
      (node (ref "IC2") (pin "25") (pinfunction "__CLK3_25") (pintype "input"))
    )
    (net (code "247") (name "unconnected-(IC2-__CLK4-Pad91)") (class "Default")
      (node (ref "IC2") (pin "91") (pinfunction "__CLK4_91") (pintype "input"))
    )
    (net (code "248") (name "unconnected-(IC2-__CLK5-Pad90)") (class "Default")
      (node (ref "IC2") (pin "90") (pinfunction "__CLK5_90") (pintype "input"))
    )
    (net (code "249") (name "unconnected-(IC2-__CLK6-Pad89)") (class "Default")
      (node (ref "IC2") (pin "89") (pinfunction "__CLK6_89") (pintype "input"))
    )
    (net (code "250") (name "unconnected-(IC2-__CLK7-Pad88)") (class "Default")
      (node (ref "IC2") (pin "88") (pinfunction "__CLK7_88") (pintype "input"))
    )
    (net (code "251") (name "unconnected-(IC2-__IO_67-Pad120)") (class "Default")
      (node (ref "IC2") (pin "120") (pinfunction "__IO_67_120") (pintype "bidirectional"))
    )
    (net (code "252") (name "unconnected-(IC2-__IO_82-Pad142)") (class "Default")
      (node (ref "IC2") (pin "142") (pinfunction "__IO_82_142") (pintype "bidirectional"))
    )
    (net (code "253") (name "unconnected-(IC7-RTS-Pad4)") (class "Default")
      (node (ref "IC7") (pin "4") (pinfunction "RTS_4") (pintype "output"))
    )
    (net (code "254") (name "unconnected-(U1-CLK-Pad20)") (class "Default")
      (node (ref "U1") (pin "20") (pinfunction "CLK_20") (pintype "bidirectional"))
    )
    (net (code "255") (name "unconnected-(U1-CMD-Pad19)") (class "Default")
      (node (ref "U1") (pin "19") (pinfunction "CMD_19") (pintype "bidirectional"))
    )
    (net (code "256") (name "unconnected-(U1-NC-Pad32)") (class "Default")
      (node (ref "U1") (pin "32") (pinfunction "NC_32") (pintype "bidirectional"))
    )
    (net (code "257") (name "unconnected-(U1-SD1-Pad22)") (class "Default")
      (node (ref "U1") (pin "22") (pinfunction "SD1_22") (pintype "bidirectional"))
    )
    (net (code "258") (name "unconnected-(U1-SD2-Pad17)") (class "Default")
      (node (ref "U1") (pin "17") (pinfunction "SD2_17") (pintype "bidirectional"))
    )
    (net (code "259") (name "unconnected-(U1-SD3-Pad18)") (class "Default")
      (node (ref "U1") (pin "18") (pinfunction "SD3_18") (pintype "bidirectional"))
    )
    (net (code "260") (name "unconnected-(U1-SDO-Pad21)") (class "Default")
      (node (ref "U1") (pin "21") (pinfunction "SDO_21") (pintype "bidirectional"))
    )
    (net (code "261") (name "unconnected-(U1-SENSOR_VN-Pad5)") (class "Default")
      (node (ref "U1") (pin "5") (pinfunction "SENSOR_VN_5") (pintype "input"))
    )
    (net (code "262") (name "unconnected-(U1-SENSOR_VP-Pad4)") (class "Default")
      (node (ref "U1") (pin "4") (pinfunction "SENSOR_VP_4") (pintype "input"))
    )
    (net (code "263") (name "unconnected-(USB1B-USBID-PadP4)") (class "Default")
      (node (ref "USB1") (pin "P4") (pinfunction "USBID_P4") (pintype "bidirectional"))
    )
    (net (code "264") (name "unconnected-(USB1B-VUSB-PadP1)") (class "Default")
      (node (ref "USB1") (pin "P1") (pinfunction "VUSB_P1") (pintype "bidirectional"))
    )
    (net (code "265") (name "unconnected-(X1-Pad4)") (class "Default")
      (node (ref "X1") (pin "4") (pinfunction "4_4") (pintype "passive"))
    )
    (net (code "266") (name "unconnected-(X1-Pad9)") (class "Default")
      (node (ref "X1") (pin "9") (pinfunction "9_9") (pintype "passive"))
    )
    (net (code "267") (name "unconnected-(X1-Pad11)") (class "Default")
      (node (ref "X1") (pin "11") (pinfunction "11_11") (pintype "passive"))
    )
    (net (code "268") (name "unconnected-(X1-Pad12)") (class "Default")
      (node (ref "X1") (pin "12") (pinfunction "12_12") (pintype "passive"))
    )
    (net (code "269") (name "unconnected-(X1-Pad15)") (class "Default")
      (node (ref "X1") (pin "15") (pinfunction "15_15") (pintype "passive"))
    )
  )
)
